# design.net
KiCad netlist of a schematic drawn in Altium Designer
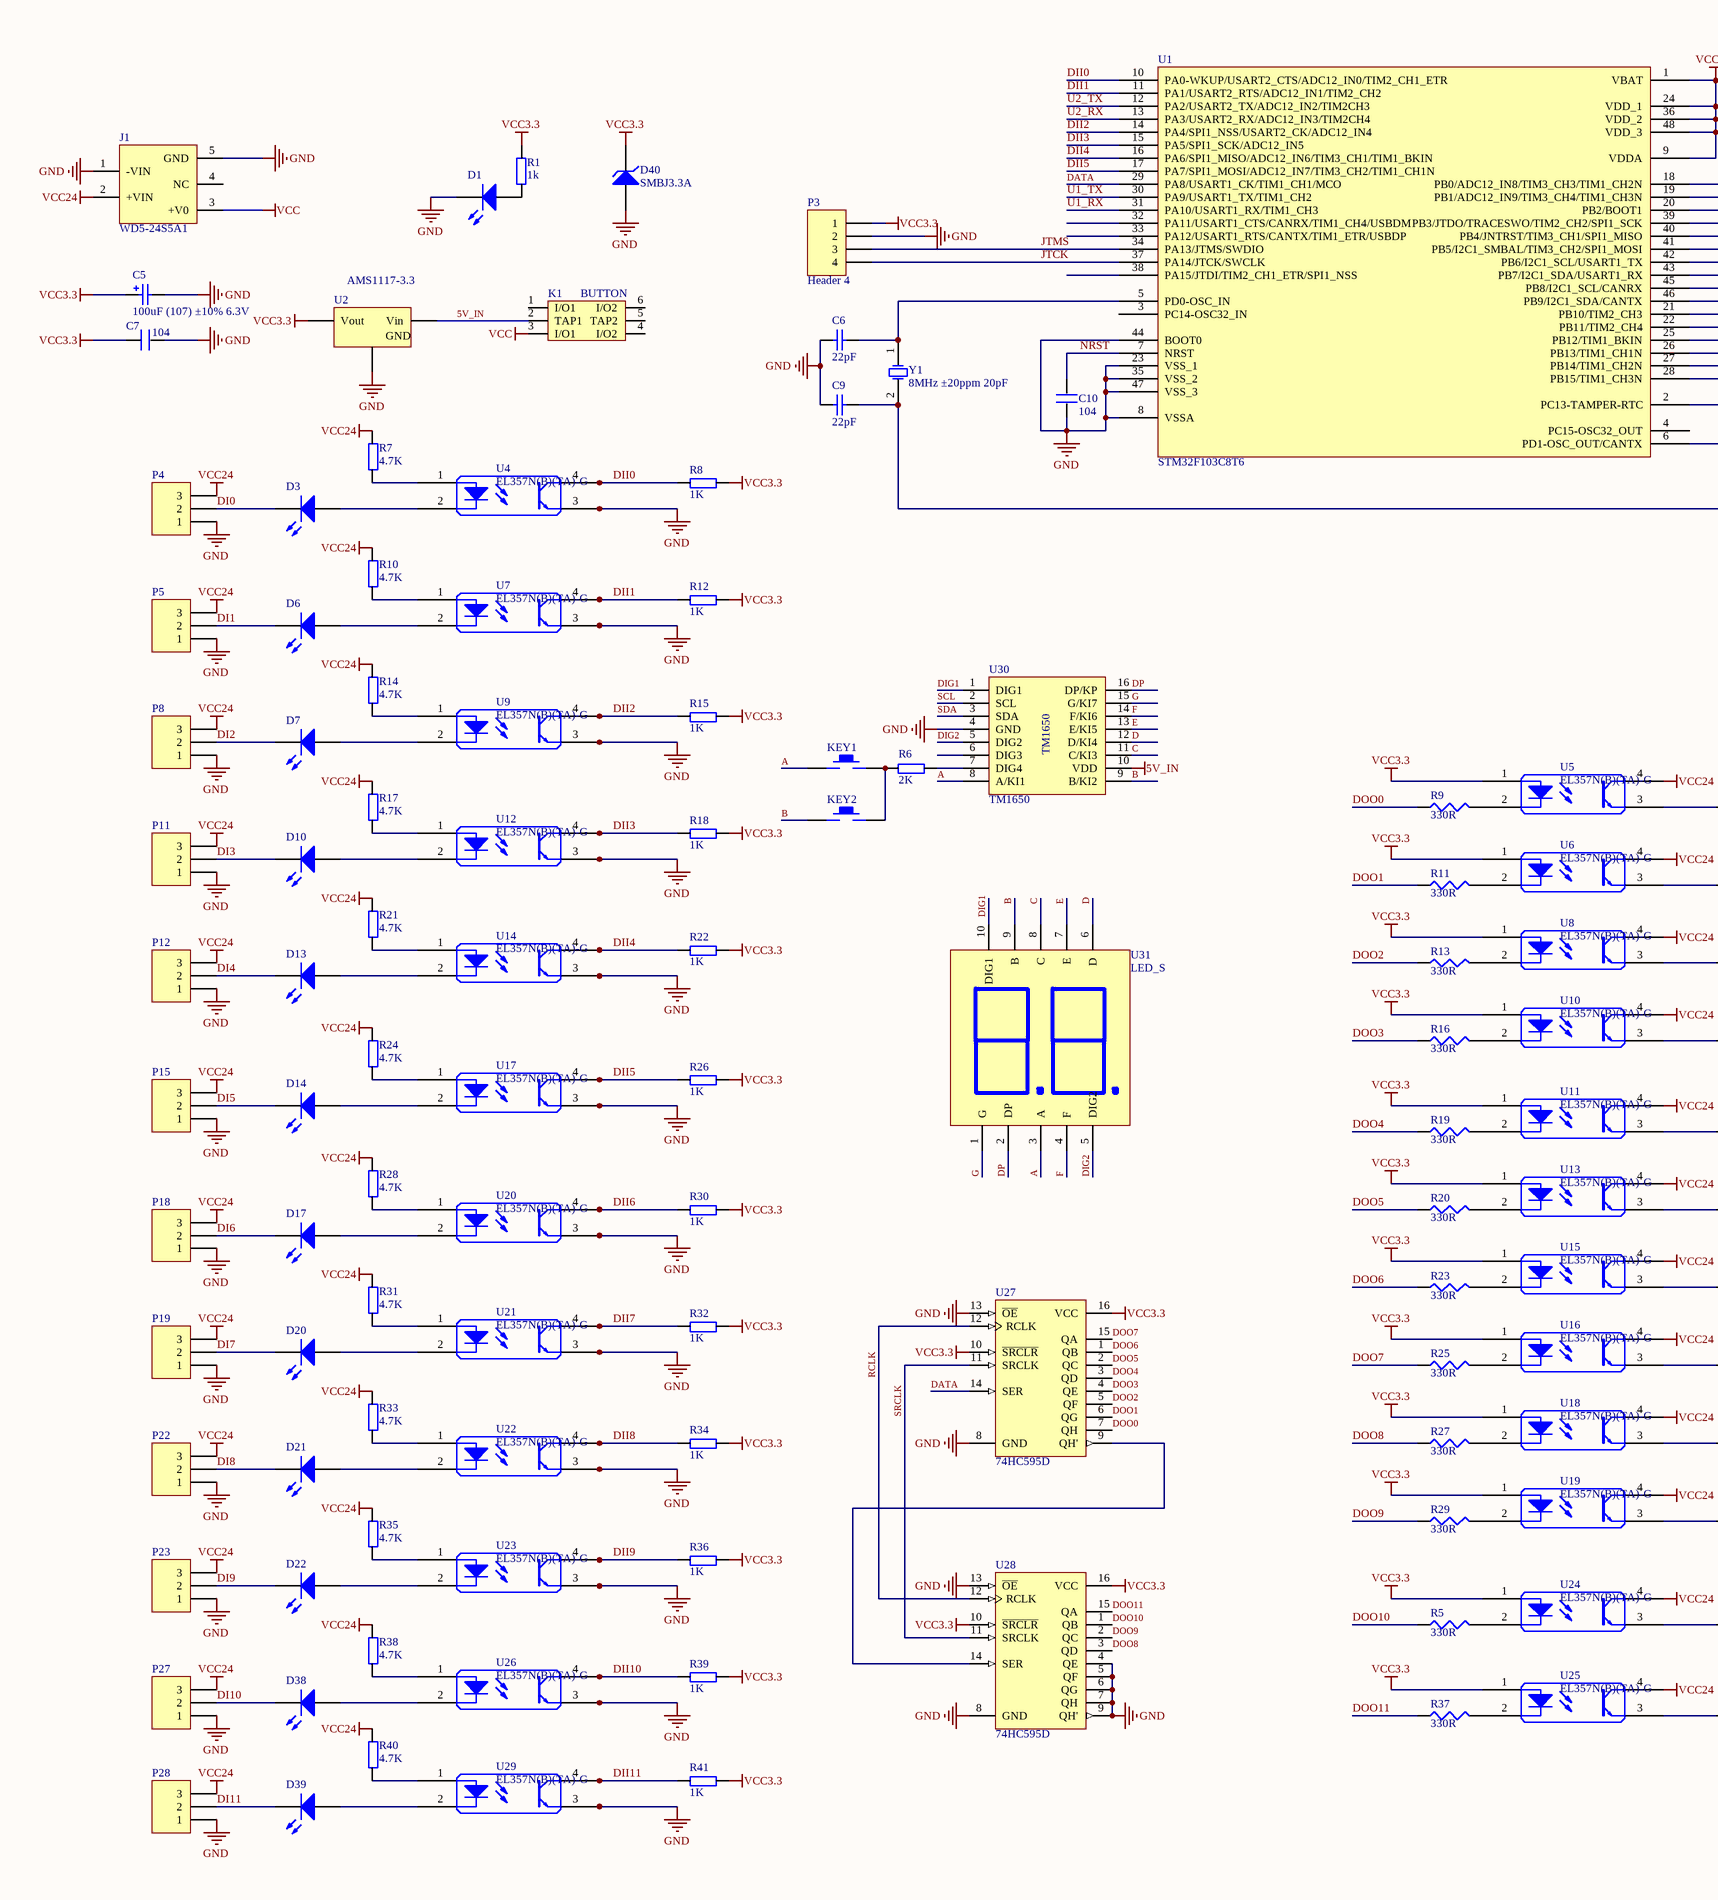
[diagram p0: 继电器板.SchDoc, left]
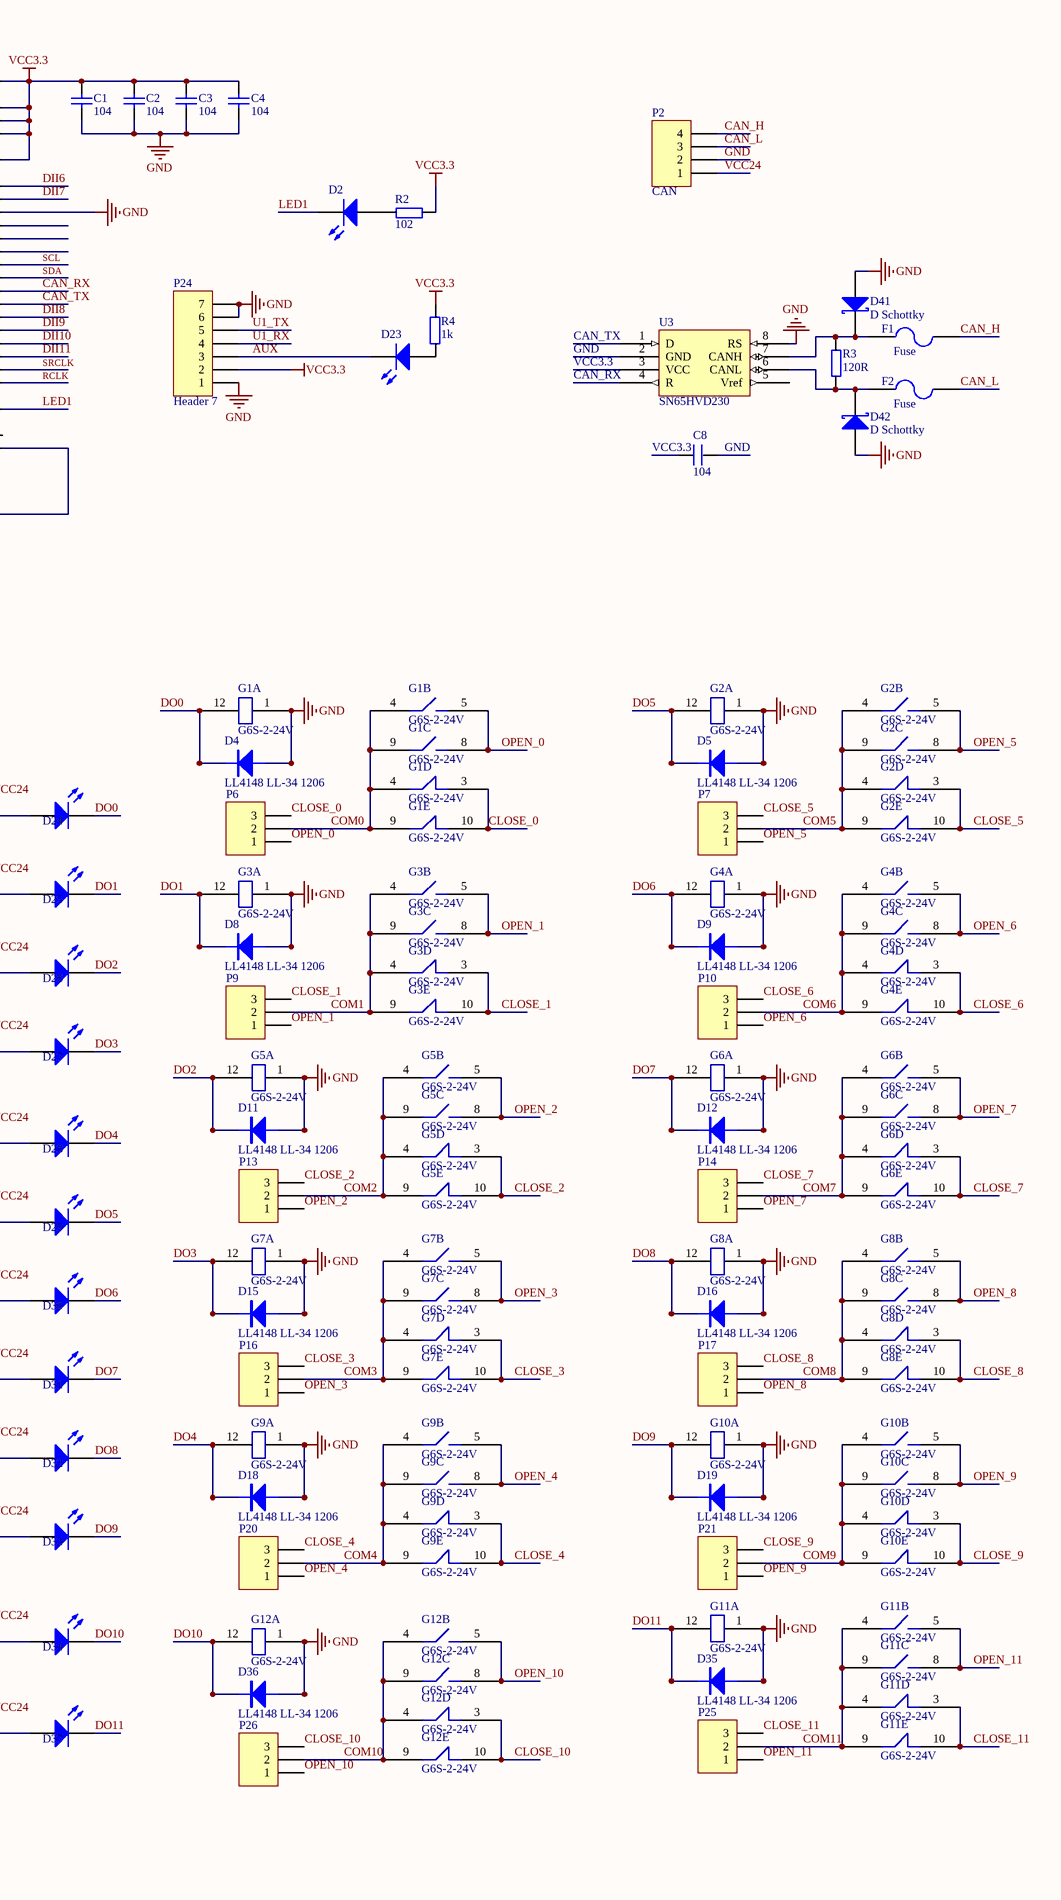
[diagram p1: 继电器板.SchDoc, right]

(export (version "E")
  (design (tool "Eeschema 10.0.6"))
  (components
    (comp (ref "C1")
      (value "104")
      (footprint "0603_C")
      (description "Capacitor")
      (fields (field (name "PUBLISHER") "Altium Limited"))
      (libsource (lib "Miscellaneous Devices") (part "Cap"))
    )
    (comp (ref "C2")
      (value "104")
      (footprint "0603_C")
      (description "Capacitor")
      (fields (field (name "PUBLISHER") "Altium Limited"))
      (libsource (lib "Miscellaneous Devices") (part "Cap"))
    )
    (comp (ref "C3")
      (value "104")
      (footprint "0603_C")
      (description "Capacitor")
      (fields (field (name "PUBLISHER") "Altium Limited"))
      (libsource (lib "Miscellaneous Devices") (part "Cap"))
    )
    (comp (ref "C4")
      (value "104")
      (footprint "0603_C")
      (description "Capacitor")
      (fields (field (name "PUBLISHER") "Altium Limited"))
      (libsource (lib "Miscellaneous Devices") (part "Cap"))
    )
    (comp (ref "C5")
      (value "100uF (107) ±10% 6.3V")
      (footprint "CASE-B_3528")
      (description "钽电容")
      (libsource (lib "Miscellaneous Devices LC") (part "3528 100uF (107) 10% 6.3V"))
    )
    (comp (ref "C6")
      (value "22pF")
      (footprint "0603_C")
      (description "Capacitor")
      (fields (field (name "PUBLISHER") "Altium Limited"))
      (libsource (lib "Miscellaneous Devices") (part "Cap"))
    )
    (comp (ref "C7") (value "104") (footprint "0603_C") (libsource (lib "WarShip V3_SCH") (part "C")))
    (comp (ref "C8")
      (value "104")
      (footprint "0603_C")
      (libsource (lib "Explorer STM32F407封装库") (part "C_3"))
    )
    (comp (ref "C9")
      (value "22pF")
      (footprint "0603_C")
      (description "Capacitor")
      (fields (field (name "PUBLISHER") "Altium Limited"))
      (libsource (lib "Miscellaneous Devices") (part "Cap"))
    )
    (comp (ref "C10") (value "104") (footprint "0603_C") (libsource (lib "Explorer STM32F407封装库") (part "C")))
    (comp (ref "D1")
      (value "蓝灯 0805")
      (footprint "LC-0805_LED_S1")
      (description "Typical INFRARED GaAs LED")
      (fields (field (name "PUBLISHER") "Altium Limited"))
      (libsource (lib "继电器板_1") (part "LED0"))
    )
    (comp (ref "D2")
      (value "红灯 0805")
      (footprint "LC-0805_LED_S1")
      (description "Typical INFRARED GaAs LED")
      (fields (field (name "PUBLISHER") "Altium Limited"))
      (libsource (lib "继电器板_1") (part "LED0"))
    )
    (comp (ref "D3")
      (value "红灯 0805")
      (footprint "LC-0805_LED_S1")
      (description "Typical INFRARED GaAs LED")
      (fields (field (name "PUBLISHER") "Altium Limited"))
      (libsource (lib "继电器板_1") (part "LED0"))
    )
    (comp (ref "D4")
      (value "LL4148 LL-34 1206")
      (footprint "LC-LL-34")
      (description "Diode")
      (libsource (lib "*") (part "DIODE"))
    )
    (comp (ref "D5")
      (value "LL4148 LL-34 1206")
      (footprint "LC-LL-34")
      (description "Diode")
      (libsource (lib "*") (part "DIODE"))
    )
    (comp (ref "D6")
      (value "红灯 0805")
      (footprint "LC-0805_LED_S1")
      (description "Typical INFRARED GaAs LED")
      (fields (field (name "PUBLISHER") "Altium Limited"))
      (libsource (lib "继电器板_1") (part "LED0"))
    )
    (comp (ref "D7")
      (value "红灯 0805")
      (footprint "LC-0805_LED_S1")
      (description "Typical INFRARED GaAs LED")
      (fields (field (name "PUBLISHER") "Altium Limited"))
      (libsource (lib "继电器板_1") (part "LED0"))
    )
    (comp (ref "D8")
      (value "LL4148 LL-34 1206")
      (footprint "LC-LL-34")
      (description "Diode")
      (libsource (lib "*") (part "DIODE"))
    )
    (comp (ref "D9")
      (value "LL4148 LL-34 1206")
      (footprint "LC-LL-34")
      (description "Diode")
      (libsource (lib "*") (part "DIODE"))
    )
    (comp (ref "D10")
      (value "红灯 0805")
      (footprint "LC-0805_LED_S1")
      (description "Typical INFRARED GaAs LED")
      (fields (field (name "PUBLISHER") "Altium Limited"))
      (libsource (lib "继电器板_1") (part "LED0"))
    )
    (comp (ref "D11")
      (value "LL4148 LL-34 1206")
      (footprint "LC-LL-34")
      (description "Diode")
      (libsource (lib "*") (part "DIODE"))
    )
    (comp (ref "D12")
      (value "LL4148 LL-34 1206")
      (footprint "LC-LL-34")
      (description "Diode")
      (libsource (lib "*") (part "DIODE"))
    )
    (comp (ref "D13")
      (value "红灯 0805")
      (footprint "LC-0805_LED_S1")
      (description "Typical INFRARED GaAs LED")
      (fields (field (name "PUBLISHER") "Altium Limited"))
      (libsource (lib "继电器板_1") (part "LED0"))
    )
    (comp (ref "D14")
      (value "红灯 0805")
      (footprint "LC-0805_LED_S1")
      (description "Typical INFRARED GaAs LED")
      (fields (field (name "PUBLISHER") "Altium Limited"))
      (libsource (lib "继电器板_1") (part "LED0"))
    )
    (comp (ref "D15")
      (value "LL4148 LL-34 1206")
      (footprint "LC-LL-34")
      (description "Diode")
      (libsource (lib "*") (part "DIODE"))
    )
    (comp (ref "D16")
      (value "LL4148 LL-34 1206")
      (footprint "LC-LL-34")
      (description "Diode")
      (libsource (lib "*") (part "DIODE"))
    )
    (comp (ref "D17")
      (value "红灯 0805")
      (footprint "LC-0805_LED_S1")
      (description "Typical INFRARED GaAs LED")
      (fields (field (name "PUBLISHER") "Altium Limited"))
      (libsource (lib "继电器板_1") (part "LED0"))
    )
    (comp (ref "D18")
      (value "LL4148 LL-34 1206")
      (footprint "LC-LL-34")
      (description "Diode")
      (libsource (lib "*") (part "DIODE"))
    )
    (comp (ref "D19")
      (value "LL4148 LL-34 1206")
      (footprint "LC-LL-34")
      (description "Diode")
      (libsource (lib "*") (part "DIODE"))
    )
    (comp (ref "D20")
      (value "红灯 0805")
      (footprint "LC-0805_LED_S1")
      (description "Typical INFRARED GaAs LED")
      (fields (field (name "PUBLISHER") "Altium Limited"))
      (libsource (lib "继电器板_1") (part "LED0"))
    )
    (comp (ref "D21")
      (value "红灯 0805")
      (footprint "LC-0805_LED_S1")
      (description "Typical INFRARED GaAs LED")
      (fields (field (name "PUBLISHER") "Altium Limited"))
      (libsource (lib "继电器板_1") (part "LED0"))
    )
    (comp (ref "D22")
      (value "红灯 0805")
      (footprint "LC-0805_LED_S1")
      (description "Typical INFRARED GaAs LED")
      (fields (field (name "PUBLISHER") "Altium Limited"))
      (libsource (lib "继电器板_1") (part "LED0"))
    )
    (comp (ref "D23")
      (value "红灯 0805")
      (footprint "LC-0805_LED_S1")
      (description "Typical INFRARED GaAs LED")
      (fields (field (name "PUBLISHER") "Altium Limited"))
      (libsource (lib "继电器板_1") (part "LED0"))
    )
    (comp (ref "D24")
      (value "红灯 0805")
      (footprint "LC-0805_LED_S1")
      (description "Typical INFRARED GaAs LED")
      (fields (field (name "PUBLISHER") "Altium Limited"))
      (libsource (lib "继电器板_1") (part "LED0"))
    )
    (comp (ref "D25")
      (value "红灯 0805")
      (footprint "LC-0805_LED_S1")
      (description "Typical INFRARED GaAs LED")
      (fields (field (name "PUBLISHER") "Altium Limited"))
      (libsource (lib "继电器板_1") (part "LED0"))
    )
    (comp (ref "D26")
      (value "红灯 0805")
      (footprint "LC-0805_LED_S1")
      (description "Typical INFRARED GaAs LED")
      (fields (field (name "PUBLISHER") "Altium Limited"))
      (libsource (lib "继电器板_1") (part "LED0"))
    )
    (comp (ref "D27")
      (value "红灯 0805")
      (footprint "LC-0805_LED_S1")
      (description "Typical INFRARED GaAs LED")
      (fields (field (name "PUBLISHER") "Altium Limited"))
      (libsource (lib "继电器板_1") (part "LED0"))
    )
    (comp (ref "D28")
      (value "红灯 0805")
      (footprint "LC-0805_LED_S1")
      (description "Typical INFRARED GaAs LED")
      (fields (field (name "PUBLISHER") "Altium Limited"))
      (libsource (lib "继电器板_1") (part "LED0"))
    )
    (comp (ref "D29")
      (value "红灯 0805")
      (footprint "LC-0805_LED_S1")
      (description "Typical INFRARED GaAs LED")
      (fields (field (name "PUBLISHER") "Altium Limited"))
      (libsource (lib "继电器板_1") (part "LED0"))
    )
    (comp (ref "D30")
      (value "红灯 0805")
      (footprint "LC-0805_LED_S1")
      (description "Typical INFRARED GaAs LED")
      (fields (field (name "PUBLISHER") "Altium Limited"))
      (libsource (lib "继电器板_1") (part "LED0"))
    )
    (comp (ref "D31")
      (value "红灯 0805")
      (footprint "LC-0805_LED_S1")
      (description "Typical INFRARED GaAs LED")
      (fields (field (name "PUBLISHER") "Altium Limited"))
      (libsource (lib "继电器板_1") (part "LED0"))
    )
    (comp (ref "D32")
      (value "红灯 0805")
      (footprint "LC-0805_LED_S1")
      (description "Typical INFRARED GaAs LED")
      (fields (field (name "PUBLISHER") "Altium Limited"))
      (libsource (lib "继电器板_1") (part "LED0"))
    )
    (comp (ref "D33")
      (value "红灯 0805")
      (footprint "LC-0805_LED_S1")
      (description "Typical INFRARED GaAs LED")
      (fields (field (name "PUBLISHER") "Altium Limited"))
      (libsource (lib "继电器板_1") (part "LED0"))
    )
    (comp (ref "D34")
      (value "红灯 0805")
      (footprint "LC-0805_LED_S1")
      (description "Typical INFRARED GaAs LED")
      (fields (field (name "PUBLISHER") "Altium Limited"))
      (libsource (lib "继电器板_1") (part "LED0"))
    )
    (comp (ref "D35")
      (value "LL4148 LL-34 1206")
      (footprint "LC-LL-34")
      (description "Diode")
      (libsource (lib "*") (part "DIODE"))
    )
    (comp (ref "D36")
      (value "LL4148 LL-34 1206")
      (footprint "LC-LL-34")
      (description "Diode")
      (libsource (lib "*") (part "DIODE"))
    )
    (comp (ref "D37")
      (value "红灯 0805")
      (footprint "LC-0805_LED_S1")
      (description "Typical INFRARED GaAs LED")
      (fields (field (name "PUBLISHER") "Altium Limited"))
      (libsource (lib "继电器板_1") (part "LED0"))
    )
    (comp (ref "D38")
      (value "红灯 0805")
      (footprint "LC-0805_LED_S1")
      (description "Typical INFRARED GaAs LED")
      (fields (field (name "PUBLISHER") "Altium Limited"))
      (libsource (lib "继电器板_1") (part "LED0"))
    )
    (comp (ref "D39")
      (value "红灯 0805")
      (footprint "LC-0805_LED_S1")
      (description "Typical INFRARED GaAs LED")
      (fields (field (name "PUBLISHER") "Altium Limited"))
      (libsource (lib "继电器板_1") (part "LED0"))
    )
    (comp (ref "D40")
      (value "SMBJ3.3A")
      (footprint "SMB(DO-214AA)_S1")
      (description "Zener Diode")
      (fields (field (name "PUBLISHER") "Altium Limited"))
      (libsource (lib "Miscellaneous Devices") (part "D Zener"))
    )
    (comp (ref "D41")
      (value "D Schottky")
      (footprint "SMB")
      (description "Schottky Diode")
      (fields (field (name "PUBLISHER") "Altium Limited"))
      (libsource (lib "Miscellaneous Devices") (part "D Schottky"))
    )
    (comp (ref "D42")
      (value "D Schottky")
      (footprint "SMB")
      (description "Schottky Diode")
      (fields (field (name "PUBLISHER") "Altium Limited"))
      (libsource (lib "Miscellaneous Devices") (part "D Schottky"))
    )
    (comp (ref "F1")
      (value "Fuse")
      (footprint "12Z-2010")
      (fields (field (name "PUBLISHER") "Altium Limited"))
      (libsource (lib "Miscellaneous Devices") (part "Fuse 2"))
    )
    (comp (ref "F2")
      (value "Fuse")
      (footprint "12Z-2010")
      (fields (field (name "PUBLISHER") "Altium Limited"))
      (libsource (lib "Miscellaneous Devices") (part "Fuse 2"))
    )
    (comp (ref "G1")
      (value "G6S-2-24V")
      (footprint "G6S-2-24V")
      (description "G5SB-14-24VDC")
      (libsource (lib "altium-import") (part "root_0__继电器板.SchLib"))
    )
    (comp (ref "G2")
      (value "G6S-2-24V")
      (footprint "G6S-2-24V")
      (description "G5SB-14-24VDC")
      (libsource (lib "altium-import") (part "root_2__继电器板.SchLib"))
    )
    (comp (ref "G3")
      (value "G6S-2-24V")
      (footprint "G6S-2-24V")
      (description "G5SB-14-24VDC")
      (libsource (lib "altium-import") (part "root_0__继电器板.SchLib"))
    )
    (comp (ref "G4")
      (value "G6S-2-24V")
      (footprint "G6S-2-24V")
      (description "G5SB-14-24VDC")
      (libsource (lib "altium-import") (part "root_0__继电器板.SchLib"))
    )
    (comp (ref "G5")
      (value "G6S-2-24V")
      (footprint "G6S-2-24V")
      (description "G5SB-14-24VDC")
      (libsource (lib "altium-import") (part "root_0__继电器板.SchLib"))
    )
    (comp (ref "G6")
      (value "G6S-2-24V")
      (footprint "G6S-2-24V")
      (description "G5SB-14-24VDC")
      (libsource (lib "altium-import") (part "root_0__继电器板.SchLib"))
    )
    (comp (ref "G7")
      (value "G6S-2-24V")
      (footprint "G6S-2-24V")
      (description "G5SB-14-24VDC")
      (libsource (lib "altium-import") (part "root_0__继电器板.SchLib"))
    )
    (comp (ref "G8")
      (value "G6S-2-24V")
      (footprint "G6S-2-24V")
      (description "G5SB-14-24VDC")
      (libsource (lib "altium-import") (part "root_2__继电器板.SchLib"))
    )
    (comp (ref "G9")
      (value "G6S-2-24V")
      (footprint "G6S-2-24V")
      (description "G5SB-14-24VDC")
      (libsource (lib "altium-import") (part "root_2__继电器板.SchLib"))
    )
    (comp (ref "G10")
      (value "G6S-2-24V")
      (footprint "G6S-2-24V")
      (description "G5SB-14-24VDC")
      (libsource (lib "altium-import") (part "root_0__继电器板.SchLib"))
    )
    (comp (ref "G11")
      (value "G6S-2-24V")
      (footprint "G6S-2-24V")
      (description "G5SB-14-24VDC")
      (libsource (lib "altium-import") (part "root_2__继电器板.SchLib"))
    )
    (comp (ref "G12")
      (value "G6S-2-24V")
      (footprint "G6S-2-24V")
      (description "G5SB-14-24VDC")
      (libsource (lib "altium-import") (part "root_0__继电器板.SchLib"))
    )
    (comp (ref "J1")
      (value "WD5-24S5A1")
      (footprint "WD5-24S3V3")
      (libsource (lib "*") (part "WD5-24S3V3A1"))
    )
    (comp (ref "K1")
      (value "BUTTON")
      (footprint "BTN8.5*8.5")
      (libsource (lib "WarShip V3_SCH") (part "BUTTON"))
    )
    (comp (ref "KEY1")
      (value "KEY_M")
      (footprint "SW_PB2_A1")
      (libsource (lib "Explorer STM32F407封装库") (part "KEY_M"))
    )
    (comp (ref "KEY2")
      (value "KEY_M")
      (footprint "SW_PB2_A1")
      (libsource (lib "Explorer STM32F407封装库") (part "KEY_M"))
    )
    (comp (ref "P2")
      (value "CAN")
      (footprint "DZ-4-3.5")
      (description "Header, 4-Pin")
      (fields (field (name "PUBLISHER") "Altium Limited"))
      (libsource (lib "Miscellaneous Connectors") (part "Header 4"))
    )
    (comp (ref "P3")
      (value "Header 4")
      (footprint "IDE4")
      (description "Header, 4-Pin")
      (fields (field (name "PUBLISHER") "Altium Limited"))
      (libsource (lib "") (part "Header 4_1"))
    )
    (comp (ref "P4")
      (value "~")
      (footprint "DZ-3-3.5")
      (description "Header, 3-Pin")
      (fields (field (name "PUBLISHER") "Altium Limited"))
      (libsource (lib "Miscellaneous Connectors") (part "Header 3"))
    )
    (comp (ref "P5")
      (value "~")
      (footprint "DZ-3-3.5")
      (description "Header, 3-Pin")
      (fields (field (name "PUBLISHER") "Altium Limited"))
      (libsource (lib "Miscellaneous Connectors") (part "Header 3"))
    )
    (comp (ref "P6")
      (value "~")
      (footprint "DZ-3-3.5")
      (description "Header, 3-Pin")
      (fields (field (name "PUBLISHER") "Altium Limited"))
      (libsource (lib "Miscellaneous Connectors") (part "Header 3"))
    )
    (comp (ref "P7")
      (value "~")
      (footprint "DZ-3-3.5")
      (description "Header, 3-Pin")
      (fields (field (name "PUBLISHER") "Altium Limited"))
      (libsource (lib "Miscellaneous Connectors") (part "Header 3"))
    )
    (comp (ref "P8")
      (value "~")
      (footprint "DZ-3-3.5")
      (description "Header, 3-Pin")
      (fields (field (name "PUBLISHER") "Altium Limited"))
      (libsource (lib "Miscellaneous Connectors") (part "Header 3"))
    )
    (comp (ref "P9")
      (value "~")
      (footprint "DZ-3-3.5")
      (description "Header, 3-Pin")
      (fields (field (name "PUBLISHER") "Altium Limited"))
      (libsource (lib "Miscellaneous Connectors") (part "Header 3"))
    )
    (comp (ref "P10")
      (value "~")
      (footprint "DZ-3-3.5")
      (description "Header, 3-Pin")
      (fields (field (name "PUBLISHER") "Altium Limited"))
      (libsource (lib "Miscellaneous Connectors") (part "Header 3"))
    )
    (comp (ref "P11")
      (value "~")
      (footprint "DZ-3-3.5")
      (description "Header, 3-Pin")
      (fields (field (name "PUBLISHER") "Altium Limited"))
      (libsource (lib "Miscellaneous Connectors") (part "Header 3"))
    )
    (comp (ref "P12")
      (value "~")
      (footprint "DZ-3-3.5")
      (description "Header, 3-Pin")
      (fields (field (name "PUBLISHER") "Altium Limited"))
      (libsource (lib "Miscellaneous Connectors") (part "Header 3"))
    )
    (comp (ref "P13")
      (value "~")
      (footprint "DZ-3-3.5")
      (description "Header, 3-Pin")
      (fields (field (name "PUBLISHER") "Altium Limited"))
      (libsource (lib "Miscellaneous Connectors") (part "Header 3"))
    )
    (comp (ref "P14")
      (value "~")
      (footprint "DZ-3-3.5")
      (description "Header, 3-Pin")
      (fields (field (name "PUBLISHER") "Altium Limited"))
      (libsource (lib "Miscellaneous Connectors") (part "Header 3"))
    )
    (comp (ref "P15")
      (value "~")
      (footprint "DZ-3-3.5")
      (description "Header, 3-Pin")
      (fields (field (name "PUBLISHER") "Altium Limited"))
      (libsource (lib "Miscellaneous Connectors") (part "Header 3"))
    )
    (comp (ref "P16")
      (value "~")
      (footprint "DZ-3-3.5")
      (description "Header, 3-Pin")
      (fields (field (name "PUBLISHER") "Altium Limited"))
      (libsource (lib "Miscellaneous Connectors") (part "Header 3"))
    )
    (comp (ref "P17")
      (value "~")
      (footprint "DZ-3-3.5")
      (description "Header, 3-Pin")
      (fields (field (name "PUBLISHER") "Altium Limited"))
      (libsource (lib "Miscellaneous Connectors") (part "Header 3"))
    )
    (comp (ref "P18")
      (value "~")
      (footprint "DZ-3-3.5")
      (description "Header, 3-Pin")
      (fields (field (name "PUBLISHER") "Altium Limited"))
      (libsource (lib "Miscellaneous Connectors") (part "Header 3"))
    )
    (comp (ref "P19")
      (value "~")
      (footprint "DZ-3-3.5")
      (description "Header, 3-Pin")
      (fields (field (name "PUBLISHER") "Altium Limited"))
      (libsource (lib "Miscellaneous Connectors") (part "Header 3"))
    )
    (comp (ref "P20")
      (value "~")
      (footprint "DZ-3-3.5")
      (description "Header, 3-Pin")
      (fields (field (name "PUBLISHER") "Altium Limited"))
      (libsource (lib "Miscellaneous Connectors") (part "Header 3"))
    )
    (comp (ref "P21")
      (value "~")
      (footprint "DZ-3-3.5")
      (description "Header, 3-Pin")
      (fields (field (name "PUBLISHER") "Altium Limited"))
      (libsource (lib "Miscellaneous Connectors") (part "Header 3"))
    )
    (comp (ref "P22")
      (value "~")
      (footprint "DZ-3-3.5")
      (description "Header, 3-Pin")
      (fields (field (name "PUBLISHER") "Altium Limited"))
      (libsource (lib "Miscellaneous Connectors") (part "Header 3"))
    )
    (comp (ref "P23")
      (value "~")
      (footprint "DZ-3-3.5")
      (description "Header, 3-Pin")
      (fields (field (name "PUBLISHER") "Altium Limited"))
      (libsource (lib "Miscellaneous Connectors") (part "Header 3"))
    )
    (comp (ref "P24")
      (value "Header 7")
      (footprint "AS50-T27")
      (description "Header, 7-Pin")
      (fields (field (name "PUBLISHER") "Altium Limited"))
      (libsource (lib "Miscellaneous Connectors") (part "Header 7"))
    )
    (comp (ref "P25")
      (value "~")
      (footprint "DZ-3-3.5")
      (description "Header, 3-Pin")
      (fields (field (name "PUBLISHER") "Altium Limited"))
      (libsource (lib "Miscellaneous Connectors") (part "Header 3"))
    )
    (comp (ref "P26")
      (value "~")
      (footprint "DZ-3-3.5")
      (description "Header, 3-Pin")
      (fields (field (name "PUBLISHER") "Altium Limited"))
      (libsource (lib "Miscellaneous Connectors") (part "Header 3"))
    )
    (comp (ref "P27")
      (value "~")
      (footprint "DZ-3-3.5")
      (description "Header, 3-Pin")
      (fields (field (name "PUBLISHER") "Altium Limited"))
      (libsource (lib "Miscellaneous Connectors") (part "Header 3"))
    )
    (comp (ref "P28")
      (value "~")
      (footprint "DZ-3-3.5")
      (description "Header, 3-Pin")
      (fields (field (name "PUBLISHER") "Altium Limited"))
      (libsource (lib "Miscellaneous Connectors") (part "Header 3"))
    )
    (comp (ref "R1") (value "1k") (footprint "0603_R") (libsource (lib "Explorer STM32F407封装库") (part "R_2")))
    (comp (ref "R2")
      (value "102")
      (footprint "0603_R")
      (libsource (lib "Explorer STM32F407封装库") (part "R_2"))
    )
    (comp (ref "R3") (value "120R") (footprint "0805") (libsource (lib "Explorer STM32F407封装库") (part "R_2")))
    (comp (ref "R4") (value "1k") (footprint "0603_R") (libsource (lib "Explorer STM32F407封装库") (part "R_2")))
    (comp (ref "R5") (value "330R") (footprint "0603_R") (libsource (lib "*") (part "RES1")))
    (comp (ref "R6") (value "2K") (footprint "0603_R") (libsource (lib "Explorer STM32F407封装库") (part "R_2")))
    (comp (ref "R7")
      (value "4.7K")
      (footprint "0603_R")
      (libsource (lib "Explorer STM32F407封装库") (part "R_2"))
    )
    (comp (ref "R8") (value "1K") (footprint "0603_R") (libsource (lib "Explorer STM32F407封装库") (part "R_2")))
    (comp (ref "R9") (value "330R") (footprint "0603_R") (libsource (lib "*") (part "RES1")))
    (comp (ref "R10")
      (value "4.7K")
      (footprint "0603_R")
      (libsource (lib "Explorer STM32F407封装库") (part "R_2"))
    )
    (comp (ref "R11") (value "330R") (footprint "0603_R") (libsource (lib "*") (part "RES1")))
    (comp (ref "R12")
      (value "1K")
      (footprint "0603_R")
      (libsource (lib "Explorer STM32F407封装库") (part "R_2"))
    )
    (comp (ref "R13") (value "330R") (footprint "0603_R") (libsource (lib "*") (part "RES1")))
    (comp (ref "R14")
      (value "4.7K")
      (footprint "0603_R")
      (libsource (lib "Explorer STM32F407封装库") (part "R_2"))
    )
    (comp (ref "R15")
      (value "1K")
      (footprint "0603_R")
      (libsource (lib "Explorer STM32F407封装库") (part "R_2"))
    )
    (comp (ref "R16") (value "330R") (footprint "0603_R") (libsource (lib "*") (part "RES1")))
    (comp (ref "R17")
      (value "4.7K")
      (footprint "0603_R")
      (libsource (lib "Explorer STM32F407封装库") (part "R_2"))
    )
    (comp (ref "R18")
      (value "1K")
      (footprint "0603_R")
      (libsource (lib "Explorer STM32F407封装库") (part "R_2"))
    )
    (comp (ref "R19") (value "330R") (footprint "0603_R") (libsource (lib "*") (part "RES1")))
    (comp (ref "R20") (value "330R") (footprint "0603_R") (libsource (lib "*") (part "RES1")))
    (comp (ref "R21")
      (value "4.7K")
      (footprint "0603_R")
      (libsource (lib "Explorer STM32F407封装库") (part "R_2"))
    )
    (comp (ref "R22")
      (value "1K")
      (footprint "0603_R")
      (libsource (lib "Explorer STM32F407封装库") (part "R_2"))
    )
    (comp (ref "R23") (value "330R") (footprint "0603_R") (libsource (lib "*") (part "RES1")))
    (comp (ref "R24")
      (value "4.7K")
      (footprint "0603_R")
      (libsource (lib "Explorer STM32F407封装库") (part "R_2"))
    )
    (comp (ref "R25") (value "330R") (footprint "0603_R") (libsource (lib "*") (part "RES1")))
    (comp (ref "R26")
      (value "1K")
      (footprint "0603_R")
      (libsource (lib "Explorer STM32F407封装库") (part "R_2"))
    )
    (comp (ref "R27") (value "330R") (footprint "0603_R") (libsource (lib "*") (part "RES1")))
    (comp (ref "R28")
      (value "4.7K")
      (footprint "0603_R")
      (libsource (lib "Explorer STM32F407封装库") (part "R_2"))
    )
    (comp (ref "R29") (value "330R") (footprint "0603_R") (libsource (lib "*") (part "RES1")))
    (comp (ref "R30")
      (value "1K")
      (footprint "0603_R")
      (libsource (lib "Explorer STM32F407封装库") (part "R_2"))
    )
    (comp (ref "R31")
      (value "4.7K")
      (footprint "0603_R")
      (libsource (lib "Explorer STM32F407封装库") (part "R_2"))
    )
    (comp (ref "R32")
      (value "1K")
      (footprint "0603_R")
      (libsource (lib "Explorer STM32F407封装库") (part "R_2"))
    )
    (comp (ref "R33")
      (value "4.7K")
      (footprint "0603_R")
      (libsource (lib "Explorer STM32F407封装库") (part "R_2"))
    )
    (comp (ref "R34")
      (value "1K")
      (footprint "0603_R")
      (libsource (lib "Explorer STM32F407封装库") (part "R_2"))
    )
    (comp (ref "R35")
      (value "4.7K")
      (footprint "0603_R")
      (libsource (lib "Explorer STM32F407封装库") (part "R_2"))
    )
    (comp (ref "R36")
      (value "1K")
      (footprint "0603_R")
      (libsource (lib "Explorer STM32F407封装库") (part "R_2"))
    )
    (comp (ref "R37") (value "330R") (footprint "0603_R") (libsource (lib "*") (part "RES1")))
    (comp (ref "R38")
      (value "4.7K")
      (footprint "0603_R")
      (libsource (lib "Explorer STM32F407封装库") (part "R_2"))
    )
    (comp (ref "R39")
      (value "1K")
      (footprint "0603_R")
      (libsource (lib "Explorer STM32F407封装库") (part "R_2"))
    )
    (comp (ref "R40")
      (value "4.7K")
      (footprint "0603_R")
      (libsource (lib "Explorer STM32F407封装库") (part "R_2"))
    )
    (comp (ref "R41")
      (value "1K")
      (footprint "0603_R")
      (libsource (lib "Explorer STM32F407封装库") (part "R_2"))
    )
    (comp (ref "U1")
      (value "STM32F103C8T6")
      (footprint "LC-LQFP-48")
      (libsource (lib "Schlib1") (part "stm32f103v8t6"))
    )
    (comp (ref "U2")
      (value "AMS1117-3.3")
      (footprint "SOT-223")
      (description "低压差线性稳压(LDO)")
      (libsource (lib "Miscellaneous Devices LC") (part "SOT-223 AMS1117-3.3"))
    )
    (comp (ref "U3")
      (value "SN65HVD230")
      (footprint "LC-SOIC-8_150mil")
      (libsource (lib "Explorer STM32F407封装库") (part "SN65HVD230D"))
    )
    (comp (ref "U4")
      (value "EL357N(B)(TA)-G")
      (footprint "LC-SOP-4_P2.54")
      (libsource (lib "*") (part "2701"))
    )
    (comp (ref "U5")
      (value "EL357N(B)(TA)-G")
      (footprint "LC-SOP-4_P2.54")
      (libsource (lib "*") (part "2701"))
    )
    (comp (ref "U6")
      (value "EL357N(B)(TA)-G")
      (footprint "LC-SOP-4_P2.54")
      (libsource (lib "*") (part "2701"))
    )
    (comp (ref "U7")
      (value "EL357N(B)(TA)-G")
      (footprint "LC-SOP-4_P2.54")
      (libsource (lib "*") (part "2701"))
    )
    (comp (ref "U8")
      (value "EL357N(B)(TA)-G")
      (footprint "LC-SOP-4_P2.54")
      (libsource (lib "*") (part "2701"))
    )
    (comp (ref "U9")
      (value "EL357N(B)(TA)-G")
      (footprint "LC-SOP-4_P2.54")
      (libsource (lib "*") (part "2701"))
    )
    (comp (ref "U10")
      (value "EL357N(B)(TA)-G")
      (footprint "LC-SOP-4_P2.54")
      (libsource (lib "*") (part "2701"))
    )
    (comp (ref "U11")
      (value "EL357N(B)(TA)-G")
      (footprint "LC-SOP-4_P2.54")
      (libsource (lib "*") (part "2701"))
    )
    (comp (ref "U12")
      (value "EL357N(B)(TA)-G")
      (footprint "LC-SOP-4_P2.54")
      (libsource (lib "*") (part "2701"))
    )
    (comp (ref "U13")
      (value "EL357N(B)(TA)-G")
      (footprint "LC-SOP-4_P2.54")
      (libsource (lib "*") (part "2701"))
    )
    (comp (ref "U14")
      (value "EL357N(B)(TA)-G")
      (footprint "LC-SOP-4_P2.54")
      (libsource (lib "*") (part "2701"))
    )
    (comp (ref "U15")
      (value "EL357N(B)(TA)-G")
      (footprint "LC-SOP-4_P2.54")
      (libsource (lib "*") (part "2701"))
    )
    (comp (ref "U16")
      (value "EL357N(B)(TA)-G")
      (footprint "LC-SOP-4_P2.54")
      (libsource (lib "*") (part "2701"))
    )
    (comp (ref "U17")
      (value "EL357N(B)(TA)-G")
      (footprint "LC-SOP-4_P2.54")
      (libsource (lib "*") (part "2701"))
    )
    (comp (ref "U18")
      (value "EL357N(B)(TA)-G")
      (footprint "LC-SOP-4_P2.54")
      (libsource (lib "*") (part "2701"))
    )
    (comp (ref "U19")
      (value "EL357N(B)(TA)-G")
      (footprint "LC-SOP-4_P2.54")
      (libsource (lib "*") (part "2701"))
    )
    (comp (ref "U20")
      (value "EL357N(B)(TA)-G")
      (footprint "LC-SOP-4_P2.54")
      (libsource (lib "*") (part "2701"))
    )
    (comp (ref "U21")
      (value "EL357N(B)(TA)-G")
      (footprint "LC-SOP-4_P2.54")
      (libsource (lib "*") (part "2701"))
    )
    (comp (ref "U22")
      (value "EL357N(B)(TA)-G")
      (footprint "LC-SOP-4_P2.54")
      (libsource (lib "*") (part "2701"))
    )
    (comp (ref "U23")
      (value "EL357N(B)(TA)-G")
      (footprint "LC-SOP-4_P2.54")
      (libsource (lib "*") (part "2701"))
    )
    (comp (ref "U24")
      (value "EL357N(B)(TA)-G")
      (footprint "LC-SOP-4_P2.54")
      (libsource (lib "*") (part "2701"))
    )
    (comp (ref "U25")
      (value "EL357N(B)(TA)-G")
      (footprint "LC-SOP-4_P2.54")
      (libsource (lib "*") (part "2701"))
    )
    (comp (ref "U26")
      (value "EL357N(B)(TA)-G")
      (footprint "LC-SOP-4_P2.54")
      (libsource (lib "*") (part "2701"))
    )
    (comp (ref "U27")
      (value "74HC595D")
      (footprint "SOIC-16_150mil")
      (description "74系列逻辑芯片")
      (libsource (lib "Miscellaneous Devices LC") (part "74HC595D"))
    )
    (comp (ref "U28")
      (value "74HC595D")
      (footprint "SOIC-16_150mil")
      (description "74系列逻辑芯片")
      (libsource (lib "Miscellaneous Devices LC") (part "74HC595D"))
    )
    (comp (ref "U29")
      (value "EL357N(B)(TA)-G")
      (footprint "LC-SOP-4_P2.54")
      (libsource (lib "*") (part "2701"))
    )
    (comp (ref "U30") (value "TM1650") (footprint "SO-16") (libsource (lib "继电器板_1") (part "TM1650")))
    (comp (ref "U31") (value "LED_S") (libsource (lib "继电器板_1") (part "LED_S")))
    (comp (ref "Y1")
      (value "8MHz ±20ppm 20pF")
      (footprint "SMD-5032_2P")
      (description "贴片晶振")
      (libsource (lib "Miscellaneous Devices LC") (part "SMD-5032_2P 8MHz 20ppm 20pF"))
    )
  )
  (nets
    (net (code "1") (name "/A") (class "Default")
      (node (ref "KEY1") (pin "1") (pinfunction "1_1") (pintype "passive"))
      (node (ref "U30") (pin "8") (pinfunction "A/KI1_8") (pintype "passive"))
      (node (ref "U31") (pin "3") (pinfunction "A_3") (pintype "passive"))
    )
    (net (code "2") (name "/AUX") (class "Default")
      (node (ref "D23") (pin "K") (pinfunction "K_K") (pintype "passive"))
      (node (ref "P24") (pin "3") (pinfunction "3_3") (pintype "passive"))
    )
    (net (code "3") (name "/B") (class "Default")
      (node (ref "KEY2") (pin "1") (pinfunction "1_1") (pintype "passive"))
      (node (ref "U30") (pin "9") (pinfunction "B/KI2_9") (pintype "passive"))
      (node (ref "U31") (pin "9") (pinfunction "B_9") (pintype "passive"))
    )
    (net (code "4") (name "/C") (class "Default")
      (node (ref "U30") (pin "11") (pinfunction "C/KI3_11") (pintype "passive"))
      (node (ref "U31") (pin "8") (pinfunction "C_8") (pintype "passive"))
    )
    (net (code "5") (name "/CAN_H") (class "Default")
      (node (ref "F1") (pin "1") (pinfunction "1_1") (pintype "passive"))
      (node (ref "P2") (pin "4") (pinfunction "4_4") (pintype "passive"))
    )
    (net (code "6") (name "/CAN_L") (class "Default")
      (node (ref "F2") (pin "1") (pinfunction "1_1") (pintype "passive"))
      (node (ref "P2") (pin "3") (pinfunction "3_3") (pintype "passive"))
    )
    (net (code "7") (name "/CAN_RX") (class "Default")
      (node (ref "U1") (pin "45") (pinfunction "PB8/I2C1_SCL/CANRX_45") (pintype "passive"))
      (node (ref "U3") (pin "4") (pinfunction "R_4") (pintype "output"))
    )
    (net (code "8") (name "/CAN_TX") (class "Default")
      (node (ref "U1") (pin "46") (pinfunction "PB9/I2C1_SDA/CANTX_46") (pintype "passive"))
      (node (ref "U3") (pin "1") (pinfunction "D_1") (pintype "input"))
    )
    (net (code "9") (name "/CLOSE_0") (class "Default")
      (node (ref "G1") (pin "10") (pinfunction "14_10") (pintype "passive"))
      (node (ref "G1") (pin "3") (pinfunction "14_3") (pintype "passive"))
      (node (ref "P6") (pin "3") (pinfunction "3_3") (pintype "passive"))
    )
    (net (code "10") (name "/CLOSE_1") (class "Default")
      (node (ref "G3") (pin "10") (pinfunction "14_10") (pintype "passive"))
      (node (ref "G3") (pin "3") (pinfunction "14_3") (pintype "passive"))
      (node (ref "P9") (pin "3") (pinfunction "3_3") (pintype "passive"))
    )
    (net (code "11") (name "/CLOSE_2") (class "Default")
      (node (ref "G5") (pin "10") (pinfunction "14_10") (pintype "passive"))
      (node (ref "G5") (pin "3") (pinfunction "14_3") (pintype "passive"))
      (node (ref "P13") (pin "3") (pinfunction "3_3") (pintype "passive"))
    )
    (net (code "12") (name "/CLOSE_3") (class "Default")
      (node (ref "G7") (pin "10") (pinfunction "14_10") (pintype "passive"))
      (node (ref "G7") (pin "3") (pinfunction "14_3") (pintype "passive"))
      (node (ref "P16") (pin "3") (pinfunction "3_3") (pintype "passive"))
    )
    (net (code "13") (name "/CLOSE_4") (class "Default")
      (node (ref "G9") (pin "10") (pinfunction "14_10") (pintype "passive"))
      (node (ref "G9") (pin "3") (pinfunction "14_3") (pintype "passive"))
      (node (ref "P20") (pin "3") (pinfunction "3_3") (pintype "passive"))
    )
    (net (code "14") (name "/CLOSE_5") (class "Default")
      (node (ref "G2") (pin "10") (pinfunction "14_10") (pintype "passive"))
      (node (ref "G2") (pin "3") (pinfunction "14_3") (pintype "passive"))
      (node (ref "P7") (pin "3") (pinfunction "3_3") (pintype "passive"))
    )
    (net (code "15") (name "/CLOSE_6") (class "Default")
      (node (ref "G4") (pin "10") (pinfunction "14_10") (pintype "passive"))
      (node (ref "G4") (pin "3") (pinfunction "14_3") (pintype "passive"))
      (node (ref "P10") (pin "3") (pinfunction "3_3") (pintype "passive"))
    )
    (net (code "16") (name "/CLOSE_7") (class "Default")
      (node (ref "G6") (pin "10") (pinfunction "14_10") (pintype "passive"))
      (node (ref "G6") (pin "3") (pinfunction "14_3") (pintype "passive"))
      (node (ref "P14") (pin "3") (pinfunction "3_3") (pintype "passive"))
    )
    (net (code "17") (name "/CLOSE_8") (class "Default")
      (node (ref "G8") (pin "10") (pinfunction "14_10") (pintype "passive"))
      (node (ref "G8") (pin "3") (pinfunction "14_3") (pintype "passive"))
      (node (ref "P17") (pin "3") (pinfunction "3_3") (pintype "passive"))
    )
    (net (code "18") (name "/CLOSE_9") (class "Default")
      (node (ref "G10") (pin "10") (pinfunction "14_10") (pintype "passive"))
      (node (ref "G10") (pin "3") (pinfunction "14_3") (pintype "passive"))
      (node (ref "P21") (pin "3") (pinfunction "3_3") (pintype "passive"))
    )
    (net (code "19") (name "/CLOSE_10") (class "Default")
      (node (ref "G12") (pin "10") (pinfunction "14_10") (pintype "passive"))
      (node (ref "G12") (pin "3") (pinfunction "14_3") (pintype "passive"))
      (node (ref "P26") (pin "3") (pinfunction "3_3") (pintype "passive"))
    )
    (net (code "20") (name "/CLOSE_11") (class "Default")
      (node (ref "G11") (pin "10") (pinfunction "14_10") (pintype "passive"))
      (node (ref "G11") (pin "3") (pinfunction "14_3") (pintype "passive"))
      (node (ref "P25") (pin "3") (pinfunction "3_3") (pintype "passive"))
    )
    (net (code "21") (name "/COM0") (class "Default")
      (node (ref "G1") (pin "4") (pinfunction "13_4") (pintype "passive"))
      (node (ref "G1") (pin "9") (pinfunction "13_9") (pintype "passive"))
      (node (ref "P6") (pin "2") (pinfunction "2_2") (pintype "passive"))
    )
    (net (code "22") (name "/COM1") (class "Default")
      (node (ref "G3") (pin "4") (pinfunction "13_4") (pintype "passive"))
      (node (ref "G3") (pin "9") (pinfunction "13_9") (pintype "passive"))
      (node (ref "P9") (pin "2") (pinfunction "2_2") (pintype "passive"))
    )
    (net (code "23") (name "/COM2") (class "Default")
      (node (ref "G5") (pin "4") (pinfunction "13_4") (pintype "passive"))
      (node (ref "G5") (pin "9") (pinfunction "13_9") (pintype "passive"))
      (node (ref "P13") (pin "2") (pinfunction "2_2") (pintype "passive"))
    )
    (net (code "24") (name "/COM3") (class "Default")
      (node (ref "G7") (pin "4") (pinfunction "13_4") (pintype "passive"))
      (node (ref "G7") (pin "9") (pinfunction "13_9") (pintype "passive"))
      (node (ref "P16") (pin "2") (pinfunction "2_2") (pintype "passive"))
    )
    (net (code "25") (name "/COM4") (class "Default")
      (node (ref "G9") (pin "4") (pinfunction "13_4") (pintype "passive"))
      (node (ref "G9") (pin "9") (pinfunction "13_9") (pintype "passive"))
      (node (ref "P20") (pin "2") (pinfunction "2_2") (pintype "passive"))
    )
    (net (code "26") (name "/COM5") (class "Default")
      (node (ref "G2") (pin "4") (pinfunction "13_4") (pintype "passive"))
      (node (ref "G2") (pin "9") (pinfunction "13_9") (pintype "passive"))
      (node (ref "P7") (pin "2") (pinfunction "2_2") (pintype "passive"))
    )
    (net (code "27") (name "/COM6") (class "Default")
      (node (ref "G4") (pin "4") (pinfunction "13_4") (pintype "passive"))
      (node (ref "G4") (pin "9") (pinfunction "13_9") (pintype "passive"))
      (node (ref "P10") (pin "2") (pinfunction "2_2") (pintype "passive"))
    )
    (net (code "28") (name "/COM7") (class "Default")
      (node (ref "G6") (pin "4") (pinfunction "13_4") (pintype "passive"))
      (node (ref "G6") (pin "9") (pinfunction "13_9") (pintype "passive"))
      (node (ref "P14") (pin "2") (pinfunction "2_2") (pintype "passive"))
    )
    (net (code "29") (name "/COM8") (class "Default")
      (node (ref "G8") (pin "4") (pinfunction "13_4") (pintype "passive"))
      (node (ref "G8") (pin "9") (pinfunction "13_9") (pintype "passive"))
      (node (ref "P17") (pin "2") (pinfunction "2_2") (pintype "passive"))
    )
    (net (code "30") (name "/COM9") (class "Default")
      (node (ref "G10") (pin "4") (pinfunction "13_4") (pintype "passive"))
      (node (ref "G10") (pin "9") (pinfunction "13_9") (pintype "passive"))
      (node (ref "P21") (pin "2") (pinfunction "2_2") (pintype "passive"))
    )
    (net (code "31") (name "/COM10") (class "Default")
      (node (ref "G12") (pin "4") (pinfunction "13_4") (pintype "passive"))
      (node (ref "G12") (pin "9") (pinfunction "13_9") (pintype "passive"))
      (node (ref "P26") (pin "2") (pinfunction "2_2") (pintype "passive"))
    )
    (net (code "32") (name "/COM11") (class "Default")
      (node (ref "G11") (pin "4") (pinfunction "13_4") (pintype "passive"))
      (node (ref "G11") (pin "9") (pinfunction "13_9") (pintype "passive"))
      (node (ref "P25") (pin "2") (pinfunction "2_2") (pintype "passive"))
    )
    (net (code "33") (name "/D") (class "Default")
      (node (ref "U30") (pin "12") (pinfunction "D/KI4_12") (pintype "passive"))
      (node (ref "U31") (pin "6") (pinfunction "D_6") (pintype "passive"))
    )
    (net (code "34") (name "/DATA") (class "Default")
      (node (ref "U1") (pin "29") (pinfunction "PA8/USART1_CK/TIM1_CH1/MCO_29") (pintype "passive"))
      (node (ref "U27") (pin "14") (pinfunction "SER_14") (pintype "input"))
    )
    (net (code "35") (name "/DI0") (class "Default")
      (node (ref "D3") (pin "K") (pinfunction "K_K") (pintype "passive"))
      (node (ref "P4") (pin "2") (pinfunction "2_2") (pintype "passive"))
    )
    (net (code "36") (name "/DI1") (class "Default")
      (node (ref "D6") (pin "K") (pinfunction "K_K") (pintype "passive"))
      (node (ref "P5") (pin "2") (pinfunction "2_2") (pintype "passive"))
    )
    (net (code "37") (name "/DI2") (class "Default")
      (node (ref "D7") (pin "K") (pinfunction "K_K") (pintype "passive"))
      (node (ref "P8") (pin "2") (pinfunction "2_2") (pintype "passive"))
    )
    (net (code "38") (name "/DI3") (class "Default")
      (node (ref "D10") (pin "K") (pinfunction "K_K") (pintype "passive"))
      (node (ref "P11") (pin "2") (pinfunction "2_2") (pintype "passive"))
    )
    (net (code "39") (name "/DI4") (class "Default")
      (node (ref "D13") (pin "K") (pinfunction "K_K") (pintype "passive"))
      (node (ref "P12") (pin "2") (pinfunction "2_2") (pintype "passive"))
    )
    (net (code "40") (name "/DI5") (class "Default")
      (node (ref "D14") (pin "K") (pinfunction "K_K") (pintype "passive"))
      (node (ref "P15") (pin "2") (pinfunction "2_2") (pintype "passive"))
    )
    (net (code "41") (name "/DI6") (class "Default")
      (node (ref "D17") (pin "K") (pinfunction "K_K") (pintype "passive"))
      (node (ref "P18") (pin "2") (pinfunction "2_2") (pintype "passive"))
    )
    (net (code "42") (name "/DI7") (class "Default")
      (node (ref "D20") (pin "K") (pinfunction "K_K") (pintype "passive"))
      (node (ref "P19") (pin "2") (pinfunction "2_2") (pintype "passive"))
    )
    (net (code "43") (name "/DI8") (class "Default")
      (node (ref "D21") (pin "K") (pinfunction "K_K") (pintype "passive"))
      (node (ref "P22") (pin "2") (pinfunction "2_2") (pintype "passive"))
    )
    (net (code "44") (name "/DI9") (class "Default")
      (node (ref "D22") (pin "K") (pinfunction "K_K") (pintype "passive"))
      (node (ref "P23") (pin "2") (pinfunction "2_2") (pintype "passive"))
    )
    (net (code "45") (name "/DI10") (class "Default")
      (node (ref "D38") (pin "K") (pinfunction "K_K") (pintype "passive"))
      (node (ref "P27") (pin "2") (pinfunction "2_2") (pintype "passive"))
    )
    (net (code "46") (name "/DI11") (class "Default")
      (node (ref "D39") (pin "K") (pinfunction "K_K") (pintype "passive"))
      (node (ref "P28") (pin "2") (pinfunction "2_2") (pintype "passive"))
    )
    (net (code "47") (name "/DIG1") (class "Default")
      (node (ref "U30") (pin "1") (pinfunction "DIG1_1") (pintype "passive"))
      (node (ref "U31") (pin "10") (pinfunction "DIG1_10") (pintype "passive"))
    )
    (net (code "48") (name "/DIG2") (class "Default")
      (node (ref "U30") (pin "5") (pinfunction "DIG2_5") (pintype "passive"))
      (node (ref "U31") (pin "5") (pinfunction "DIG2_5") (pintype "passive"))
    )
    (net (code "49") (name "/DII0") (class "Default")
      (node (ref "R8") (pin "1") (pintype "passive"))
      (node (ref "U1") (pin "10") (pinfunction "PA0-WKUP/USART2_CTS/ADC12_IN0/TIM2_CH1_ETR_10") (pintype "passive"))
      (node (ref "U4") (pin "4") (pintype "passive"))
    )
    (net (code "50") (name "/DII1") (class "Default")
      (node (ref "R12") (pin "1") (pintype "passive"))
      (node (ref "U1") (pin "11") (pinfunction "PA1/USART2_RTS/ADC12_IN1/TIM2_CH2_11") (pintype "passive"))
      (node (ref "U7") (pin "4") (pintype "passive"))
    )
    (net (code "51") (name "/DII2") (class "Default")
      (node (ref "R15") (pin "1") (pintype "passive"))
      (node (ref "U1") (pin "14") (pinfunction "PA4/SPI1_NSS/USART2_CK/ADC12_IN4_14") (pintype "passive"))
      (node (ref "U9") (pin "4") (pintype "passive"))
    )
    (net (code "52") (name "/DII3") (class "Default")
      (node (ref "R18") (pin "1") (pintype "passive"))
      (node (ref "U1") (pin "15") (pinfunction "PA5/SPI1_SCK/ADC12_IN5_15") (pintype "passive"))
      (node (ref "U12") (pin "4") (pintype "passive"))
    )
    (net (code "53") (name "/DII4") (class "Default")
      (node (ref "R22") (pin "1") (pintype "passive"))
      (node (ref "U1") (pin "16") (pinfunction "PA6/SPI1_MISO/ADC12_IN6/TIM3_CH1/TIM1_BKIN_16") (pintype "passive"))
      (node (ref "U14") (pin "4") (pintype "passive"))
    )
    (net (code "54") (name "/DII5") (class "Default")
      (node (ref "R26") (pin "1") (pintype "passive"))
      (node (ref "U1") (pin "17") (pinfunction "PA7/SPI1_MOSI/ADC12_IN7/TIM3_CH2/TIM1_CH1N_17") (pintype "passive"))
      (node (ref "U17") (pin "4") (pintype "passive"))
    )
    (net (code "55") (name "/DII6") (class "Default")
      (node (ref "R30") (pin "1") (pintype "passive"))
      (node (ref "U1") (pin "18") (pinfunction "PB0/ADC12_IN8/TIM3_CH3/TIM1_CH2N_18") (pintype "passive"))
      (node (ref "U20") (pin "4") (pintype "passive"))
    )
    (net (code "56") (name "/DII7") (class "Default")
      (node (ref "R32") (pin "1") (pintype "passive"))
      (node (ref "U1") (pin "19") (pinfunction "PB1/ADC12_IN9/TIM3_CH4/TIM1_CH3N_19") (pintype "passive"))
      (node (ref "U21") (pin "4") (pintype "passive"))
    )
    (net (code "57") (name "/DII8") (class "Default")
      (node (ref "R34") (pin "1") (pintype "passive"))
      (node (ref "U1") (pin "21") (pinfunction "PB10/TIM2_CH3_21") (pintype "passive"))
      (node (ref "U22") (pin "4") (pintype "passive"))
    )
    (net (code "58") (name "/DII9") (class "Default")
      (node (ref "R36") (pin "1") (pintype "passive"))
      (node (ref "U1") (pin "22") (pinfunction "PB11/TIM2_CH4_22") (pintype "passive"))
      (node (ref "U23") (pin "4") (pintype "passive"))
    )
    (net (code "59") (name "/DII10") (class "Default")
      (node (ref "R39") (pin "1") (pintype "passive"))
      (node (ref "U1") (pin "25") (pinfunction "PB12/TIM1_BKIN_25") (pintype "passive"))
      (node (ref "U26") (pin "4") (pintype "passive"))
    )
    (net (code "60") (name "/DII11") (class "Default")
      (node (ref "R41") (pin "1") (pintype "passive"))
      (node (ref "U1") (pin "26") (pinfunction "PB13/TIM1_CH1N_26") (pintype "passive"))
      (node (ref "U29") (pin "4") (pintype "passive"))
    )
    (net (code "61") (name "/DO0") (class "Default")
      (node (ref "D24") (pin "K") (pinfunction "K_K") (pintype "passive"))
      (node (ref "D4") (pin "2") (pinfunction "K_2") (pintype "passive"))
      (node (ref "G1") (pin "12") (pinfunction "2_12") (pintype "passive"))
    )
    (net (code "62") (name "/DO1") (class "Default")
      (node (ref "D25") (pin "K") (pinfunction "K_K") (pintype "passive"))
      (node (ref "D8") (pin "2") (pinfunction "K_2") (pintype "passive"))
      (node (ref "G3") (pin "12") (pinfunction "2_12") (pintype "passive"))
    )
    (net (code "63") (name "/DO2") (class "Default")
      (node (ref "D11") (pin "2") (pinfunction "K_2") (pintype "passive"))
      (node (ref "D26") (pin "K") (pinfunction "K_K") (pintype "passive"))
      (node (ref "G5") (pin "12") (pinfunction "2_12") (pintype "passive"))
    )
    (net (code "64") (name "/DO3") (class "Default")
      (node (ref "D15") (pin "2") (pinfunction "K_2") (pintype "passive"))
      (node (ref "D27") (pin "K") (pinfunction "K_K") (pintype "passive"))
      (node (ref "G7") (pin "12") (pinfunction "2_12") (pintype "passive"))
    )
    (net (code "65") (name "/DO4") (class "Default")
      (node (ref "D18") (pin "2") (pinfunction "K_2") (pintype "passive"))
      (node (ref "D28") (pin "K") (pinfunction "K_K") (pintype "passive"))
      (node (ref "G9") (pin "12") (pinfunction "2_12") (pintype "passive"))
    )
    (net (code "66") (name "/DO5") (class "Default")
      (node (ref "D29") (pin "K") (pinfunction "K_K") (pintype "passive"))
      (node (ref "D5") (pin "2") (pinfunction "K_2") (pintype "passive"))
      (node (ref "G2") (pin "12") (pinfunction "2_12") (pintype "passive"))
    )
    (net (code "67") (name "/DO6") (class "Default")
      (node (ref "D30") (pin "K") (pinfunction "K_K") (pintype "passive"))
      (node (ref "D9") (pin "2") (pinfunction "K_2") (pintype "passive"))
      (node (ref "G4") (pin "12") (pinfunction "2_12") (pintype "passive"))
    )
    (net (code "68") (name "/DO7") (class "Default")
      (node (ref "D12") (pin "2") (pinfunction "K_2") (pintype "passive"))
      (node (ref "D31") (pin "K") (pinfunction "K_K") (pintype "passive"))
      (node (ref "G6") (pin "12") (pinfunction "2_12") (pintype "passive"))
    )
    (net (code "69") (name "/DO8") (class "Default")
      (node (ref "D16") (pin "2") (pinfunction "K_2") (pintype "passive"))
      (node (ref "D32") (pin "K") (pinfunction "K_K") (pintype "passive"))
      (node (ref "G8") (pin "12") (pinfunction "2_12") (pintype "passive"))
    )
    (net (code "70") (name "/DO9") (class "Default")
      (node (ref "D19") (pin "2") (pinfunction "K_2") (pintype "passive"))
      (node (ref "D33") (pin "K") (pinfunction "K_K") (pintype "passive"))
      (node (ref "G10") (pin "12") (pinfunction "2_12") (pintype "passive"))
    )
    (net (code "71") (name "/DO10") (class "Default")
      (node (ref "D34") (pin "K") (pinfunction "K_K") (pintype "passive"))
      (node (ref "D36") (pin "2") (pinfunction "K_2") (pintype "passive"))
      (node (ref "G12") (pin "12") (pinfunction "2_12") (pintype "passive"))
    )
    (net (code "72") (name "/DO11") (class "Default")
      (node (ref "D35") (pin "2") (pinfunction "K_2") (pintype "passive"))
      (node (ref "D37") (pin "K") (pinfunction "K_K") (pintype "passive"))
      (node (ref "G11") (pin "12") (pinfunction "2_12") (pintype "passive"))
    )
    (net (code "73") (name "/DOO0") (class "Default")
      (node (ref "R9") (pin "1") (pintype "passive"))
      (node (ref "U27") (pin "7") (pinfunction "QH_7") (pintype "tri_state"))
    )
    (net (code "74") (name "/DOO1") (class "Default")
      (node (ref "R11") (pin "1") (pintype "passive"))
      (node (ref "U27") (pin "6") (pinfunction "QG_6") (pintype "tri_state"))
    )
    (net (code "75") (name "/DOO2") (class "Default")
      (node (ref "R13") (pin "1") (pintype "passive"))
      (node (ref "U27") (pin "5") (pinfunction "QF_5") (pintype "tri_state"))
    )
    (net (code "76") (name "/DOO3") (class "Default")
      (node (ref "R16") (pin "1") (pintype "passive"))
      (node (ref "U27") (pin "4") (pinfunction "QE_4") (pintype "tri_state"))
    )
    (net (code "77") (name "/DOO4") (class "Default")
      (node (ref "R19") (pin "1") (pintype "passive"))
      (node (ref "U27") (pin "3") (pinfunction "QD_3") (pintype "tri_state"))
    )
    (net (code "78") (name "/DOO5") (class "Default")
      (node (ref "R20") (pin "1") (pintype "passive"))
      (node (ref "U27") (pin "2") (pinfunction "QC_2") (pintype "tri_state"))
    )
    (net (code "79") (name "/DOO6") (class "Default")
      (node (ref "R23") (pin "1") (pintype "passive"))
      (node (ref "U27") (pin "1") (pinfunction "QB_1") (pintype "tri_state"))
    )
    (net (code "80") (name "/DOO7") (class "Default")
      (node (ref "R25") (pin "1") (pintype "passive"))
      (node (ref "U27") (pin "15") (pinfunction "QA_15") (pintype "tri_state"))
    )
    (net (code "81") (name "/DOO8") (class "Default")
      (node (ref "R27") (pin "1") (pintype "passive"))
      (node (ref "U28") (pin "3") (pinfunction "QD_3") (pintype "tri_state"))
    )
    (net (code "82") (name "/DOO9") (class "Default")
      (node (ref "R29") (pin "1") (pintype "passive"))
      (node (ref "U28") (pin "2") (pinfunction "QC_2") (pintype "tri_state"))
    )
    (net (code "83") (name "/DOO10") (class "Default")
      (node (ref "R5") (pin "1") (pintype "passive"))
      (node (ref "U28") (pin "1") (pinfunction "QB_1") (pintype "tri_state"))
    )
    (net (code "84") (name "/DOO11") (class "Default")
      (node (ref "R37") (pin "1") (pintype "passive"))
      (node (ref "U28") (pin "15") (pinfunction "QA_15") (pintype "tri_state"))
    )
    (net (code "85") (name "/DP") (class "Default")
      (node (ref "U30") (pin "16") (pinfunction "DP/KP_16") (pintype "passive"))
      (node (ref "U31") (pin "2") (pinfunction "DP_2") (pintype "passive"))
    )
    (net (code "86") (name "/E") (class "Default")
      (node (ref "U30") (pin "13") (pinfunction "E/KI5_13") (pintype "passive"))
      (node (ref "U31") (pin "7") (pinfunction "E_7") (pintype "passive"))
    )
    (net (code "87") (name "/F") (class "Default")
      (node (ref "U30") (pin "14") (pinfunction "F/KI6_14") (pintype "passive"))
      (node (ref "U31") (pin "4") (pinfunction "F_4") (pintype "passive"))
    )
    (net (code "88") (name "/G") (class "Default")
      (node (ref "U30") (pin "15") (pinfunction "G/KI7_15") (pintype "passive"))
      (node (ref "U31") (pin "1") (pinfunction "G_1") (pintype "passive"))
    )
    (net (code "89") (name "/JTCK") (class "Default")
      (node (ref "P3") (pin "4") (pinfunction "4_4") (pintype "passive"))
      (node (ref "U1") (pin "37") (pinfunction "PA14/JTCK/SWCLK_37") (pintype "passive"))
    )
    (net (code "90") (name "/JTMS") (class "Default")
      (node (ref "P3") (pin "3") (pinfunction "3_3") (pintype "passive"))
      (node (ref "U1") (pin "34") (pinfunction "PA13/JTMS/SWDIO_34") (pintype "passive"))
    )
    (net (code "91") (name "/LED1") (class "Default")
      (node (ref "D2") (pin "K") (pinfunction "K_K") (pintype "passive"))
      (node (ref "U1") (pin "2") (pinfunction "PC13-TAMPER-RTC_2") (pintype "passive"))
    )
    (net (code "92") (name "/NRST") (class "Default")
      (node (ref "C10") (pin "2") (pintype "passive"))
      (node (ref "U1") (pin "7") (pinfunction "NRST_7") (pintype "passive"))
    )
    (net (code "93") (name "/OPEN_0") (class "Default")
      (node (ref "G1") (pin "5") (pinfunction "14_5") (pintype "passive"))
      (node (ref "G1") (pin "8") (pinfunction "14_8") (pintype "passive"))
      (node (ref "P6") (pin "1") (pinfunction "1_1") (pintype "passive"))
    )
    (net (code "94") (name "/OPEN_1") (class "Default")
      (node (ref "G3") (pin "5") (pinfunction "14_5") (pintype "passive"))
      (node (ref "G3") (pin "8") (pinfunction "14_8") (pintype "passive"))
      (node (ref "P9") (pin "1") (pinfunction "1_1") (pintype "passive"))
    )
    (net (code "95") (name "/OPEN_2") (class "Default")
      (node (ref "G5") (pin "5") (pinfunction "14_5") (pintype "passive"))
      (node (ref "G5") (pin "8") (pinfunction "14_8") (pintype "passive"))
      (node (ref "P13") (pin "1") (pinfunction "1_1") (pintype "passive"))
    )
    (net (code "96") (name "/OPEN_3") (class "Default")
      (node (ref "G7") (pin "5") (pinfunction "14_5") (pintype "passive"))
      (node (ref "G7") (pin "8") (pinfunction "14_8") (pintype "passive"))
      (node (ref "P16") (pin "1") (pinfunction "1_1") (pintype "passive"))
    )
    (net (code "97") (name "/OPEN_4") (class "Default")
      (node (ref "G9") (pin "5") (pinfunction "14_5") (pintype "passive"))
      (node (ref "G9") (pin "8") (pinfunction "14_8") (pintype "passive"))
      (node (ref "P20") (pin "1") (pinfunction "1_1") (pintype "passive"))
    )
    (net (code "98") (name "/OPEN_5") (class "Default")
      (node (ref "G2") (pin "5") (pinfunction "14_5") (pintype "passive"))
      (node (ref "G2") (pin "8") (pinfunction "14_8") (pintype "passive"))
      (node (ref "P7") (pin "1") (pinfunction "1_1") (pintype "passive"))
    )
    (net (code "99") (name "/OPEN_6") (class "Default")
      (node (ref "G4") (pin "5") (pinfunction "14_5") (pintype "passive"))
      (node (ref "G4") (pin "8") (pinfunction "14_8") (pintype "passive"))
      (node (ref "P10") (pin "1") (pinfunction "1_1") (pintype "passive"))
    )
    (net (code "100") (name "/OPEN_7") (class "Default")
      (node (ref "G6") (pin "5") (pinfunction "14_5") (pintype "passive"))
      (node (ref "G6") (pin "8") (pinfunction "14_8") (pintype "passive"))
      (node (ref "P14") (pin "1") (pinfunction "1_1") (pintype "passive"))
    )
    (net (code "101") (name "/OPEN_8") (class "Default")
      (node (ref "G8") (pin "5") (pinfunction "14_5") (pintype "passive"))
      (node (ref "G8") (pin "8") (pinfunction "14_8") (pintype "passive"))
      (node (ref "P17") (pin "1") (pinfunction "1_1") (pintype "passive"))
    )
    (net (code "102") (name "/OPEN_9") (class "Default")
      (node (ref "G10") (pin "5") (pinfunction "14_5") (pintype "passive"))
      (node (ref "G10") (pin "8") (pinfunction "14_8") (pintype "passive"))
      (node (ref "P21") (pin "1") (pinfunction "1_1") (pintype "passive"))
    )
    (net (code "103") (name "/OPEN_10") (class "Default")
      (node (ref "G12") (pin "5") (pinfunction "14_5") (pintype "passive"))
      (node (ref "G12") (pin "8") (pinfunction "14_8") (pintype "passive"))
      (node (ref "P26") (pin "1") (pinfunction "1_1") (pintype "passive"))
    )
    (net (code "104") (name "/OPEN_11") (class "Default")
      (node (ref "G11") (pin "5") (pinfunction "14_5") (pintype "passive"))
      (node (ref "G11") (pin "8") (pinfunction "14_8") (pintype "passive"))
      (node (ref "P25") (pin "1") (pinfunction "1_1") (pintype "passive"))
    )
    (net (code "105") (name "/RCLK") (class "Default")
      (node (ref "U1") (pin "28") (pinfunction "PB15/TIM1_CH3N_28") (pintype "passive"))
      (node (ref "U27") (pin "12") (pinfunction "RCLK_12") (pintype "input"))
      (node (ref "U28") (pin "12") (pinfunction "RCLK_12") (pintype "input"))
    )
    (net (code "106") (name "/SCL") (class "Default")
      (node (ref "U1") (pin "42") (pinfunction "PB6/I2C1_SCL/USART1_TX_42") (pintype "passive"))
      (node (ref "U30") (pin "2") (pinfunction "SCL_2") (pintype "passive"))
    )
    (net (code "107") (name "/SDA") (class "Default")
      (node (ref "U1") (pin "43") (pinfunction "PB7/I2C1_SDA/USART1_RX_43") (pintype "passive"))
      (node (ref "U30") (pin "3") (pinfunction "SDA_3") (pintype "passive"))
    )
    (net (code "108") (name "/SRCLK") (class "Default")
      (node (ref "U1") (pin "27") (pinfunction "PB14/TIM1_CH2N_27") (pintype "passive"))
      (node (ref "U27") (pin "11") (pinfunction "SRCLK_11") (pintype "input"))
      (node (ref "U28") (pin "11") (pinfunction "SRCLK_11") (pintype "input"))
    )
    (net (code "109") (name "/U1_RX") (class "Default")
      (node (ref "P24") (pin "4") (pinfunction "4_4") (pintype "passive"))
      (node (ref "U1") (pin "31") (pinfunction "PA10/USART1_RX/TIM1_CH3_31") (pintype "passive"))
    )
    (net (code "110") (name "/U1_TX") (class "Default")
      (node (ref "P24") (pin "5") (pinfunction "5_5") (pintype "passive"))
      (node (ref "U1") (pin "30") (pinfunction "PA9/USART1_TX/TIM1_CH2_30") (pintype "passive"))
    )
    (net (code "111") (name "/U2_RX") (class "Default")
      (node (ref "U1") (pin "13") (pinfunction "PA3/USART2_RX/ADC12_IN3/TIM2CH4_13") (pintype "passive"))
    )
    (net (code "112") (name "/U2_TX") (class "Default")
      (node (ref "U1") (pin "12") (pinfunction "PA2/USART2_TX/ADC12_IN2/TIM2CH3_12") (pintype "passive"))
    )
    (net (code "113") (name "5V_IN") (class "Default")
      (node (ref "K1") (pin "2") (pinfunction "TAP1_2") (pintype "passive"))
      (node (ref "U2") (pin "3") (pinfunction "Vin_3") (pintype "passive"))
      (node (ref "U30") (pin "10") (pinfunction "VDD_10") (pintype "passive"))
    )
    (net (code "114") (name "GND") (class "Default")
      (node (ref "C1") (pin "2") (pinfunction "2_2") (pintype "passive"))
      (node (ref "C10") (pin "1") (pintype "passive"))
      (node (ref "C2") (pin "2") (pinfunction "2_2") (pintype "passive"))
      (node (ref "C3") (pin "2") (pinfunction "2_2") (pintype "passive"))
      (node (ref "C4") (pin "2") (pinfunction "2_2") (pintype "passive"))
      (node (ref "C5") (pin "2") (pinfunction "2_2") (pintype "passive"))
      (node (ref "C6") (pin "2") (pinfunction "2_2") (pintype "passive"))
      (node (ref "C7") (pin "1") (pintype "passive"))
      (node (ref "C8") (pin "2") (pintype "passive"))
      (node (ref "C9") (pin "2") (pinfunction "2_2") (pintype "passive"))
      (node (ref "D1") (pin "K") (pinfunction "K_K") (pintype "passive"))
      (node (ref "D11") (pin "1") (pinfunction "A_1") (pintype "passive"))
      (node (ref "D12") (pin "1") (pinfunction "A_1") (pintype "passive"))
      (node (ref "D15") (pin "1") (pinfunction "A_1") (pintype "passive"))
      (node (ref "D16") (pin "1") (pinfunction "A_1") (pintype "passive"))
      (node (ref "D18") (pin "1") (pinfunction "A_1") (pintype "passive"))
      (node (ref "D19") (pin "1") (pinfunction "A_1") (pintype "passive"))
      (node (ref "D35") (pin "1") (pinfunction "A_1") (pintype "passive"))
      (node (ref "D36") (pin "1") (pinfunction "A_1") (pintype "passive"))
      (node (ref "D4") (pin "1") (pinfunction "A_1") (pintype "passive"))
      (node (ref "D40") (pin "1") (pinfunction "A_1") (pintype "passive"))
      (node (ref "D41") (pin "1") (pinfunction "A_1") (pintype "passive"))
      (node (ref "D42") (pin "1") (pinfunction "A_1") (pintype "passive"))
      (node (ref "D5") (pin "1") (pinfunction "A_1") (pintype "passive"))
      (node (ref "D8") (pin "1") (pinfunction "A_1") (pintype "passive"))
      (node (ref "D9") (pin "1") (pinfunction "A_1") (pintype "passive"))
      (node (ref "G1") (pin "1") (pinfunction "17_1") (pintype "passive"))
      (node (ref "G10") (pin "1") (pinfunction "17_1") (pintype "passive"))
      (node (ref "G11") (pin "1") (pinfunction "17_1") (pintype "passive"))
      (node (ref "G12") (pin "1") (pinfunction "17_1") (pintype "passive"))
      (node (ref "G2") (pin "1") (pinfunction "17_1") (pintype "passive"))
      (node (ref "G3") (pin "1") (pinfunction "17_1") (pintype "passive"))
      (node (ref "G4") (pin "1") (pinfunction "17_1") (pintype "passive"))
      (node (ref "G5") (pin "1") (pinfunction "17_1") (pintype "passive"))
      (node (ref "G6") (pin "1") (pinfunction "17_1") (pintype "passive"))
      (node (ref "G7") (pin "1") (pinfunction "17_1") (pintype "passive"))
      (node (ref "G8") (pin "1") (pinfunction "17_1") (pintype "passive"))
      (node (ref "G9") (pin "1") (pinfunction "17_1") (pintype "passive"))
      (node (ref "J1") (pin "1") (pinfunction "-VIN_1") (pintype "passive"))
      (node (ref "J1") (pin "5") (pinfunction "GND_5") (pintype "passive"))
      (node (ref "P11") (pin "1") (pinfunction "1_1") (pintype "passive"))
      (node (ref "P12") (pin "1") (pinfunction "1_1") (pintype "passive"))
      (node (ref "P15") (pin "1") (pinfunction "1_1") (pintype "passive"))
      (node (ref "P18") (pin "1") (pinfunction "1_1") (pintype "passive"))
      (node (ref "P19") (pin "1") (pinfunction "1_1") (pintype "passive"))
      (node (ref "P2") (pin "2") (pinfunction "2_2") (pintype "passive"))
      (node (ref "P22") (pin "1") (pinfunction "1_1") (pintype "passive"))
      (node (ref "P23") (pin "1") (pinfunction "1_1") (pintype "passive"))
      (node (ref "P24") (pin "1") (pinfunction "1_1") (pintype "passive"))
      (node (ref "P24") (pin "6") (pinfunction "6_6") (pintype "passive"))
      (node (ref "P24") (pin "7") (pinfunction "7_7") (pintype "passive"))
      (node (ref "P27") (pin "1") (pinfunction "1_1") (pintype "passive"))
      (node (ref "P28") (pin "1") (pinfunction "1_1") (pintype "passive"))
      (node (ref "P3") (pin "2") (pinfunction "2_2") (pintype "passive"))
      (node (ref "P4") (pin "1") (pinfunction "1_1") (pintype "passive"))
      (node (ref "P5") (pin "1") (pinfunction "1_1") (pintype "passive"))
      (node (ref "P8") (pin "1") (pinfunction "1_1") (pintype "passive"))
      (node (ref "U1") (pin "20") (pinfunction "PB2/BOOT1_20") (pintype "passive"))
      (node (ref "U1") (pin "23") (pinfunction "VSS_1_23") (pintype "passive"))
      (node (ref "U1") (pin "35") (pinfunction "VSS_2_35") (pintype "passive"))
      (node (ref "U1") (pin "44") (pinfunction "BOOT0_44") (pintype "passive"))
      (node (ref "U1") (pin "47") (pinfunction "VSS_3_47") (pintype "passive"))
      (node (ref "U1") (pin "8") (pinfunction "VSSA_8") (pintype "passive"))
      (node (ref "U12") (pin "3") (pintype "passive"))
      (node (ref "U14") (pin "3") (pintype "passive"))
      (node (ref "U17") (pin "3") (pintype "passive"))
      (node (ref "U2") (pin "1") (pinfunction "GND_1") (pintype "passive"))
      (node (ref "U20") (pin "3") (pintype "passive"))
      (node (ref "U21") (pin "3") (pintype "passive"))
      (node (ref "U22") (pin "3") (pintype "passive"))
      (node (ref "U23") (pin "3") (pintype "passive"))
      (node (ref "U26") (pin "3") (pintype "passive"))
      (node (ref "U27") (pin "13") (pinfunction "~{OE}_13") (pintype "input"))
      (node (ref "U27") (pin "8") (pinfunction "GND_8") (pintype "power_in"))
      (node (ref "U28") (pin "13") (pinfunction "~{OE}_13") (pintype "input"))
      (node (ref "U28") (pin "4") (pinfunction "QE_4") (pintype "tri_state"))
      (node (ref "U28") (pin "5") (pinfunction "QF_5") (pintype "tri_state"))
      (node (ref "U28") (pin "6") (pinfunction "QG_6") (pintype "tri_state"))
      (node (ref "U28") (pin "7") (pinfunction "QH_7") (pintype "tri_state"))
      (node (ref "U28") (pin "8") (pinfunction "GND_8") (pintype "power_in"))
      (node (ref "U28") (pin "9") (pinfunction "QH'_9") (pintype "output"))
      (node (ref "U29") (pin "3") (pintype "passive"))
      (node (ref "U3") (pin "2") (pinfunction "GND_2") (pintype "power_in"))
      (node (ref "U3") (pin "8") (pinfunction "RS_8") (pintype "input"))
      (node (ref "U30") (pin "4") (pinfunction "GND_4") (pintype "passive"))
      (node (ref "U4") (pin "3") (pintype "passive"))
      (node (ref "U7") (pin "3") (pintype "passive"))
      (node (ref "U9") (pin "3") (pintype "passive"))
    )
    (net (code "115") (name "Net-(D1-PadA)") (class "Default")
      (node (ref "D1") (pin "A") (pinfunction "A_A") (pintype "passive"))
      (node (ref "R1") (pin "2") (pintype "passive"))
    )
    (net (code "116") (name "Net-(D2-PadA)") (class "Default")
      (node (ref "D2") (pin "A") (pinfunction "A_A") (pintype "passive"))
      (node (ref "R2") (pin "1") (pintype "passive"))
    )
    (net (code "117") (name "Net-(D3-PadA)") (class "Default")
      (node (ref "D3") (pin "A") (pinfunction "A_A") (pintype "passive"))
      (node (ref "U4") (pin "2") (pintype "passive"))
    )
    (net (code "118") (name "Net-(D6-PadA)") (class "Default")
      (node (ref "D6") (pin "A") (pinfunction "A_A") (pintype "passive"))
      (node (ref "U7") (pin "2") (pintype "passive"))
    )
    (net (code "119") (name "Net-(D7-PadA)") (class "Default")
      (node (ref "D7") (pin "A") (pinfunction "A_A") (pintype "passive"))
      (node (ref "U9") (pin "2") (pintype "passive"))
    )
    (net (code "120") (name "Net-(D10-PadA)") (class "Default")
      (node (ref "D10") (pin "A") (pinfunction "A_A") (pintype "passive"))
      (node (ref "U12") (pin "2") (pintype "passive"))
    )
    (net (code "121") (name "Net-(D13-PadA)") (class "Default")
      (node (ref "D13") (pin "A") (pinfunction "A_A") (pintype "passive"))
      (node (ref "U14") (pin "2") (pintype "passive"))
    )
    (net (code "122") (name "Net-(D14-PadA)") (class "Default")
      (node (ref "D14") (pin "A") (pinfunction "A_A") (pintype "passive"))
      (node (ref "U17") (pin "2") (pintype "passive"))
    )
    (net (code "123") (name "Net-(D17-PadA)") (class "Default")
      (node (ref "D17") (pin "A") (pinfunction "A_A") (pintype "passive"))
      (node (ref "U20") (pin "2") (pintype "passive"))
    )
    (net (code "124") (name "Net-(D20-PadA)") (class "Default")
      (node (ref "D20") (pin "A") (pinfunction "A_A") (pintype "passive"))
      (node (ref "U21") (pin "2") (pintype "passive"))
    )
    (net (code "125") (name "Net-(D21-PadA)") (class "Default")
      (node (ref "D21") (pin "A") (pinfunction "A_A") (pintype "passive"))
      (node (ref "U22") (pin "2") (pintype "passive"))
    )
    (net (code "126") (name "Net-(D22-PadA)") (class "Default")
      (node (ref "D22") (pin "A") (pinfunction "A_A") (pintype "passive"))
      (node (ref "U23") (pin "2") (pintype "passive"))
    )
    (net (code "127") (name "Net-(D23-PadA)") (class "Default")
      (node (ref "D23") (pin "A") (pinfunction "A_A") (pintype "passive"))
      (node (ref "R4") (pin "2") (pintype "passive"))
    )
    (net (code "128") (name "Net-(D24-PadA)") (class "Default")
      (node (ref "D24") (pin "A") (pinfunction "A_A") (pintype "passive"))
      (node (ref "U5") (pin "3") (pintype "passive"))
    )
    (net (code "129") (name "Net-(D25-PadA)") (class "Default")
      (node (ref "D25") (pin "A") (pinfunction "A_A") (pintype "passive"))
      (node (ref "U6") (pin "3") (pintype "passive"))
    )
    (net (code "130") (name "Net-(D26-PadA)") (class "Default")
      (node (ref "D26") (pin "A") (pinfunction "A_A") (pintype "passive"))
      (node (ref "U8") (pin "3") (pintype "passive"))
    )
    (net (code "131") (name "Net-(D27-PadA)") (class "Default")
      (node (ref "D27") (pin "A") (pinfunction "A_A") (pintype "passive"))
      (node (ref "U10") (pin "3") (pintype "passive"))
    )
    (net (code "132") (name "Net-(D28-PadA)") (class "Default")
      (node (ref "D28") (pin "A") (pinfunction "A_A") (pintype "passive"))
      (node (ref "U11") (pin "3") (pintype "passive"))
    )
    (net (code "133") (name "Net-(D29-PadA)") (class "Default")
      (node (ref "D29") (pin "A") (pinfunction "A_A") (pintype "passive"))
      (node (ref "U13") (pin "3") (pintype "passive"))
    )
    (net (code "134") (name "Net-(D30-PadA)") (class "Default")
      (node (ref "D30") (pin "A") (pinfunction "A_A") (pintype "passive"))
      (node (ref "U15") (pin "3") (pintype "passive"))
    )
    (net (code "135") (name "Net-(D31-PadA)") (class "Default")
      (node (ref "D31") (pin "A") (pinfunction "A_A") (pintype "passive"))
      (node (ref "U16") (pin "3") (pintype "passive"))
    )
    (net (code "136") (name "Net-(D32-PadA)") (class "Default")
      (node (ref "D32") (pin "A") (pinfunction "A_A") (pintype "passive"))
      (node (ref "U18") (pin "3") (pintype "passive"))
    )
    (net (code "137") (name "Net-(D33-PadA)") (class "Default")
      (node (ref "D33") (pin "A") (pinfunction "A_A") (pintype "passive"))
      (node (ref "U19") (pin "3") (pintype "passive"))
    )
    (net (code "138") (name "Net-(D34-PadA)") (class "Default")
      (node (ref "D34") (pin "A") (pinfunction "A_A") (pintype "passive"))
      (node (ref "U24") (pin "3") (pintype "passive"))
    )
    (net (code "139") (name "Net-(D37-PadA)") (class "Default")
      (node (ref "D37") (pin "A") (pinfunction "A_A") (pintype "passive"))
      (node (ref "U25") (pin "3") (pintype "passive"))
    )
    (net (code "140") (name "Net-(D38-PadA)") (class "Default")
      (node (ref "D38") (pin "A") (pinfunction "A_A") (pintype "passive"))
      (node (ref "U26") (pin "2") (pintype "passive"))
    )
    (net (code "141") (name "Net-(D39-PadA)") (class "Default")
      (node (ref "D39") (pin "A") (pinfunction "A_A") (pintype "passive"))
      (node (ref "U29") (pin "2") (pintype "passive"))
    )
    (net (code "142") (name "Net-(D41-K)") (class "Default")
      (node (ref "D41") (pin "2") (pinfunction "K_2") (pintype "passive"))
      (node (ref "F1") (pin "2") (pinfunction "2_2") (pintype "passive"))
      (node (ref "R3") (pin "2") (pintype "passive"))
      (node (ref "U3") (pin "7") (pinfunction "CANH_7") (pintype "bidirectional"))
    )
    (net (code "143") (name "Net-(D42-K)") (class "Default")
      (node (ref "D42") (pin "2") (pinfunction "K_2") (pintype "passive"))
      (node (ref "F2") (pin "2") (pinfunction "2_2") (pintype "passive"))
      (node (ref "R3") (pin "1") (pintype "passive"))
      (node (ref "U3") (pin "6") (pinfunction "CANL_6") (pintype "bidirectional"))
    )
    (net (code "144") (name "Net-(KEY1-Pad2)") (class "Default")
      (node (ref "KEY1") (pin "2") (pinfunction "2_2") (pintype "passive"))
      (node (ref "KEY2") (pin "2") (pinfunction "2_2") (pintype "passive"))
      (node (ref "R6") (pin "1") (pintype "passive"))
    )
    (net (code "145") (name "Net-(R5-Pad2)") (class "Default")
      (node (ref "R5") (pin "2") (pintype "passive"))
      (node (ref "U24") (pin "2") (pintype "passive"))
    )
    (net (code "146") (name "Net-(R7-Pad1)") (class "Default")
      (node (ref "R7") (pin "1") (pintype "passive"))
      (node (ref "U4") (pin "1") (pintype "passive"))
    )
    (net (code "147") (name "Net-(R9-Pad2)") (class "Default")
      (node (ref "R9") (pin "2") (pintype "passive"))
      (node (ref "U5") (pin "2") (pintype "passive"))
    )
    (net (code "148") (name "Net-(R10-Pad1)") (class "Default")
      (node (ref "R10") (pin "1") (pintype "passive"))
      (node (ref "U7") (pin "1") (pintype "passive"))
    )
    (net (code "149") (name "Net-(R11-Pad2)") (class "Default")
      (node (ref "R11") (pin "2") (pintype "passive"))
      (node (ref "U6") (pin "2") (pintype "passive"))
    )
    (net (code "150") (name "Net-(R13-Pad2)") (class "Default")
      (node (ref "R13") (pin "2") (pintype "passive"))
      (node (ref "U8") (pin "2") (pintype "passive"))
    )
    (net (code "151") (name "Net-(R14-Pad1)") (class "Default")
      (node (ref "R14") (pin "1") (pintype "passive"))
      (node (ref "U9") (pin "1") (pintype "passive"))
    )
    (net (code "152") (name "Net-(R16-Pad2)") (class "Default")
      (node (ref "R16") (pin "2") (pintype "passive"))
      (node (ref "U10") (pin "2") (pintype "passive"))
    )
    (net (code "153") (name "Net-(R17-Pad1)") (class "Default")
      (node (ref "R17") (pin "1") (pintype "passive"))
      (node (ref "U12") (pin "1") (pintype "passive"))
    )
    (net (code "154") (name "Net-(R19-Pad2)") (class "Default")
      (node (ref "R19") (pin "2") (pintype "passive"))
      (node (ref "U11") (pin "2") (pintype "passive"))
    )
    (net (code "155") (name "Net-(R20-Pad2)") (class "Default")
      (node (ref "R20") (pin "2") (pintype "passive"))
      (node (ref "U13") (pin "2") (pintype "passive"))
    )
    (net (code "156") (name "Net-(R21-Pad1)") (class "Default")
      (node (ref "R21") (pin "1") (pintype "passive"))
      (node (ref "U14") (pin "1") (pintype "passive"))
    )
    (net (code "157") (name "Net-(R23-Pad2)") (class "Default")
      (node (ref "R23") (pin "2") (pintype "passive"))
      (node (ref "U15") (pin "2") (pintype "passive"))
    )
    (net (code "158") (name "Net-(R24-Pad1)") (class "Default")
      (node (ref "R24") (pin "1") (pintype "passive"))
      (node (ref "U17") (pin "1") (pintype "passive"))
    )
    (net (code "159") (name "Net-(R25-Pad2)") (class "Default")
      (node (ref "R25") (pin "2") (pintype "passive"))
      (node (ref "U16") (pin "2") (pintype "passive"))
    )
    (net (code "160") (name "Net-(R27-Pad2)") (class "Default")
      (node (ref "R27") (pin "2") (pintype "passive"))
      (node (ref "U18") (pin "2") (pintype "passive"))
    )
    (net (code "161") (name "Net-(R28-Pad1)") (class "Default")
      (node (ref "R28") (pin "1") (pintype "passive"))
      (node (ref "U20") (pin "1") (pintype "passive"))
    )
    (net (code "162") (name "Net-(R29-Pad2)") (class "Default")
      (node (ref "R29") (pin "2") (pintype "passive"))
      (node (ref "U19") (pin "2") (pintype "passive"))
    )
    (net (code "163") (name "Net-(R31-Pad1)") (class "Default")
      (node (ref "R31") (pin "1") (pintype "passive"))
      (node (ref "U21") (pin "1") (pintype "passive"))
    )
    (net (code "164") (name "Net-(R33-Pad1)") (class "Default")
      (node (ref "R33") (pin "1") (pintype "passive"))
      (node (ref "U22") (pin "1") (pintype "passive"))
    )
    (net (code "165") (name "Net-(R35-Pad1)") (class "Default")
      (node (ref "R35") (pin "1") (pintype "passive"))
      (node (ref "U23") (pin "1") (pintype "passive"))
    )
    (net (code "166") (name "Net-(R37-Pad2)") (class "Default")
      (node (ref "R37") (pin "2") (pintype "passive"))
      (node (ref "U25") (pin "2") (pintype "passive"))
    )
    (net (code "167") (name "Net-(R38-Pad1)") (class "Default")
      (node (ref "R38") (pin "1") (pintype "passive"))
      (node (ref "U26") (pin "1") (pintype "passive"))
    )
    (net (code "168") (name "Net-(R40-Pad1)") (class "Default")
      (node (ref "R40") (pin "1") (pintype "passive"))
      (node (ref "U29") (pin "1") (pintype "passive"))
    )
    (net (code "169") (name "Net-(U1-PD0-OSC_IN)") (class "Default")
      (node (ref "C6") (pin "1") (pinfunction "1_1") (pintype "passive"))
      (node (ref "U1") (pin "5") (pinfunction "PD0-OSC_IN_5") (pintype "passive"))
      (node (ref "Y1") (pin "1") (pinfunction "OSC1_1") (pintype "passive"))
    )
    (net (code "170") (name "Net-(U1-PD1-OSC_OUT{slash}CANTX)") (class "Default")
      (node (ref "C9") (pin "1") (pinfunction "1_1") (pintype "passive"))
      (node (ref "U1") (pin "6") (pinfunction "PD1-OSC_OUT/CANTX_6") (pintype "passive"))
      (node (ref "Y1") (pin "2") (pinfunction "OSC2_2") (pintype "passive"))
    )
    (net (code "171") (name "Net-(U27-QH')") (class "Default")
      (node (ref "U27") (pin "9") (pinfunction "QH'_9") (pintype "output"))
      (node (ref "U28") (pin "14") (pinfunction "SER_14") (pintype "input"))
    )
    (net (code "172") (name "Net-(U30-DIG4)") (class "Default")
      (node (ref "R6") (pin "2") (pintype "passive"))
      (node (ref "U30") (pin "7") (pinfunction "DIG4_7") (pintype "passive"))
    )
    (net (code "173") (name "VCC") (class "Default")
      (node (ref "J1") (pin "3") (pinfunction "+V0_3") (pintype "passive"))
      (node (ref "K1") (pin "3") (pinfunction "I/O1_3") (pintype "passive"))
    )
    (net (code "174") (name "VCC3.3") (class "Default")
      (node (ref "C1") (pin "1") (pinfunction "1_1") (pintype "passive"))
      (node (ref "C2") (pin "1") (pinfunction "1_1") (pintype "passive"))
      (node (ref "C3") (pin "1") (pinfunction "1_1") (pintype "passive"))
      (node (ref "C4") (pin "1") (pinfunction "1_1") (pintype "passive"))
      (node (ref "C5") (pin "1") (pinfunction "1_1") (pintype "passive"))
      (node (ref "C7") (pin "2") (pintype "passive"))
      (node (ref "C8") (pin "1") (pintype "passive"))
      (node (ref "D40") (pin "2") (pinfunction "K_2") (pintype "passive"))
      (node (ref "P24") (pin "2") (pinfunction "2_2") (pintype "passive"))
      (node (ref "P3") (pin "1") (pinfunction "1_1") (pintype "passive"))
      (node (ref "R1") (pin "1") (pintype "passive"))
      (node (ref "R12") (pin "2") (pintype "passive"))
      (node (ref "R15") (pin "2") (pintype "passive"))
      (node (ref "R18") (pin "2") (pintype "passive"))
      (node (ref "R2") (pin "2") (pintype "passive"))
      (node (ref "R22") (pin "2") (pintype "passive"))
      (node (ref "R26") (pin "2") (pintype "passive"))
      (node (ref "R30") (pin "2") (pintype "passive"))
      (node (ref "R32") (pin "2") (pintype "passive"))
      (node (ref "R34") (pin "2") (pintype "passive"))
      (node (ref "R36") (pin "2") (pintype "passive"))
      (node (ref "R39") (pin "2") (pintype "passive"))
      (node (ref "R4") (pin "1") (pintype "passive"))
      (node (ref "R41") (pin "2") (pintype "passive"))
      (node (ref "R8") (pin "2") (pintype "passive"))
      (node (ref "U1") (pin "1") (pinfunction "VBAT_1") (pintype "passive"))
      (node (ref "U1") (pin "24") (pinfunction "VDD_1_24") (pintype "passive"))
      (node (ref "U1") (pin "36") (pinfunction "VDD_2_36") (pintype "passive"))
      (node (ref "U1") (pin "48") (pinfunction "VDD_3_48") (pintype "passive"))
      (node (ref "U1") (pin "9") (pinfunction "VDDA_9") (pintype "passive"))
      (node (ref "U10") (pin "1") (pintype "passive"))
      (node (ref "U11") (pin "1") (pintype "passive"))
      (node (ref "U13") (pin "1") (pintype "passive"))
      (node (ref "U15") (pin "1") (pintype "passive"))
      (node (ref "U16") (pin "1") (pintype "passive"))
      (node (ref "U18") (pin "1") (pintype "passive"))
      (node (ref "U19") (pin "1") (pintype "passive"))
      (node (ref "U2") (pin "2") (pinfunction "Vout_2") (pintype "passive"))
      (node (ref "U24") (pin "1") (pintype "passive"))
      (node (ref "U25") (pin "1") (pintype "passive"))
      (node (ref "U27") (pin "10") (pinfunction "~{SRCLR}_10") (pintype "input"))
      (node (ref "U27") (pin "16") (pinfunction "VCC_16") (pintype "power_in"))
      (node (ref "U28") (pin "10") (pinfunction "~{SRCLR}_10") (pintype "input"))
      (node (ref "U28") (pin "16") (pinfunction "VCC_16") (pintype "power_in"))
      (node (ref "U3") (pin "3") (pinfunction "VCC_3") (pintype "power_in"))
      (node (ref "U5") (pin "1") (pintype "passive"))
      (node (ref "U6") (pin "1") (pintype "passive"))
      (node (ref "U8") (pin "1") (pintype "passive"))
    )
    (net (code "175") (name "VCC24") (class "Default")
      (node (ref "J1") (pin "2") (pinfunction "+VIN_2") (pintype "passive"))
      (node (ref "P11") (pin "3") (pinfunction "3_3") (pintype "passive"))
      (node (ref "P12") (pin "3") (pinfunction "3_3") (pintype "passive"))
      (node (ref "P15") (pin "3") (pinfunction "3_3") (pintype "passive"))
      (node (ref "P18") (pin "3") (pinfunction "3_3") (pintype "passive"))
      (node (ref "P19") (pin "3") (pinfunction "3_3") (pintype "passive"))
      (node (ref "P2") (pin "1") (pinfunction "1_1") (pintype "passive"))
      (node (ref "P22") (pin "3") (pinfunction "3_3") (pintype "passive"))
      (node (ref "P23") (pin "3") (pinfunction "3_3") (pintype "passive"))
      (node (ref "P27") (pin "3") (pinfunction "3_3") (pintype "passive"))
      (node (ref "P28") (pin "3") (pinfunction "3_3") (pintype "passive"))
      (node (ref "P4") (pin "3") (pinfunction "3_3") (pintype "passive"))
      (node (ref "P5") (pin "3") (pinfunction "3_3") (pintype "passive"))
      (node (ref "P8") (pin "3") (pinfunction "3_3") (pintype "passive"))
      (node (ref "R10") (pin "2") (pintype "passive"))
      (node (ref "R14") (pin "2") (pintype "passive"))
      (node (ref "R17") (pin "2") (pintype "passive"))
      (node (ref "R21") (pin "2") (pintype "passive"))
      (node (ref "R24") (pin "2") (pintype "passive"))
      (node (ref "R28") (pin "2") (pintype "passive"))
      (node (ref "R31") (pin "2") (pintype "passive"))
      (node (ref "R33") (pin "2") (pintype "passive"))
      (node (ref "R35") (pin "2") (pintype "passive"))
      (node (ref "R38") (pin "2") (pintype "passive"))
      (node (ref "R40") (pin "2") (pintype "passive"))
      (node (ref "R7") (pin "2") (pintype "passive"))
      (node (ref "U10") (pin "4") (pintype "passive"))
      (node (ref "U11") (pin "4") (pintype "passive"))
      (node (ref "U13") (pin "4") (pintype "passive"))
      (node (ref "U15") (pin "4") (pintype "passive"))
      (node (ref "U16") (pin "4") (pintype "passive"))
      (node (ref "U18") (pin "4") (pintype "passive"))
      (node (ref "U19") (pin "4") (pintype "passive"))
      (node (ref "U24") (pin "4") (pintype "passive"))
      (node (ref "U25") (pin "4") (pintype "passive"))
      (node (ref "U5") (pin "4") (pintype "passive"))
      (node (ref "U6") (pin "4") (pintype "passive"))
      (node (ref "U8") (pin "4") (pintype "passive"))
    )
    (net (code "176") (name "unconnected-(J1-NC-Pad4)") (class "Default")
      (node (ref "J1") (pin "4") (pinfunction "NC_4") (pintype "passive"))
    )
    (net (code "177") (name "unconnected-(K1-I{slash}O1-Pad1)") (class "Default")
      (node (ref "K1") (pin "1") (pinfunction "I/O1_1") (pintype "passive"))
    )
    (net (code "178") (name "unconnected-(K1-I{slash}O2-Pad4)") (class "Default")
      (node (ref "K1") (pin "4") (pinfunction "I/O2_4") (pintype "passive"))
    )
    (net (code "179") (name "unconnected-(K1-I{slash}O2-Pad6)") (class "Default")
      (node (ref "K1") (pin "6") (pinfunction "I/O2_6") (pintype "passive"))
    )
    (net (code "180") (name "unconnected-(K1-TAP2-Pad5)") (class "Default")
      (node (ref "K1") (pin "5") (pinfunction "TAP2_5") (pintype "passive"))
    )
    (net (code "181") (name "unconnected-(U1-PA11{slash}USART1_CTS{slash}CANRX{slash}TIM1_CH4{slash}USBDM-Pad32)") (class "Default")
      (node (ref "U1") (pin "32") (pinfunction "PA11/USART1_CTS/CANRX/TIM1_CH4/USBDM_32") (pintype "passive"))
    )
    (net (code "182") (name "unconnected-(U1-PA12{slash}USART1_RTS{slash}CANTX{slash}TIM1_ETR{slash}USBDP-Pad33)") (class "Default")
      (node (ref "U1") (pin "33") (pinfunction "PA12/USART1_RTS/CANTX/TIM1_ETR/USBDP_33") (pintype "passive"))
    )
    (net (code "183") (name "unconnected-(U1-PA15{slash}JTDI{slash}TIM2_CH1_ETR{slash}SPI1_NSS-Pad38)") (class "Default")
      (node (ref "U1") (pin "38") (pinfunction "PA15/JTDI/TIM2_CH1_ETR/SPI1_NSS_38") (pintype "passive"))
    )
    (net (code "184") (name "unconnected-(U1-PB3{slash}JTDO{slash}TRACESWO{slash}TIM2_CH2{slash}SPI1_SCK-Pad39)") (class "Default")
      (node (ref "U1") (pin "39") (pinfunction "PB3/JTDO/TRACESWO/TIM2_CH2/SPI1_SCK_39") (pintype "passive"))
    )
    (net (code "185") (name "unconnected-(U1-PB4{slash}JNTRST{slash}TIM3_CH1{slash}SPI1_MISO-Pad40)") (class "Default")
      (node (ref "U1") (pin "40") (pinfunction "PB4/JNTRST/TIM3_CH1/SPI1_MISO_40") (pintype "passive"))
    )
    (net (code "186") (name "unconnected-(U1-PB5{slash}I2C1_SMBAL{slash}TIM3_CH2{slash}SPI1_MOSI-Pad41)") (class "Default")
      (node (ref "U1") (pin "41") (pinfunction "PB5/I2C1_SMBAL/TIM3_CH2/SPI1_MOSI_41") (pintype "passive"))
    )
    (net (code "187") (name "unconnected-(U1-PC14-OSC32_IN-Pad3)") (class "Default")
      (node (ref "U1") (pin "3") (pinfunction "PC14-OSC32_IN_3") (pintype "passive"))
    )
    (net (code "188") (name "unconnected-(U1-PC15-OSC32_OUT-Pad4)") (class "Default")
      (node (ref "U1") (pin "4") (pinfunction "PC15-OSC32_OUT_4") (pintype "passive"))
    )
    (net (code "189") (name "unconnected-(U3-Vref-Pad5)") (class "Default")
      (node (ref "U3") (pin "5") (pinfunction "Vref_5") (pintype "output"))
    )
    (net (code "190") (name "unconnected-(U30-DIG3-Pad6)") (class "Default")
      (node (ref "U30") (pin "6") (pinfunction "DIG3_6") (pintype "passive"))
    )
  )
)
